# transponder-6_2_0.net
KiCad netlist of a schematic drawn in EAGLE
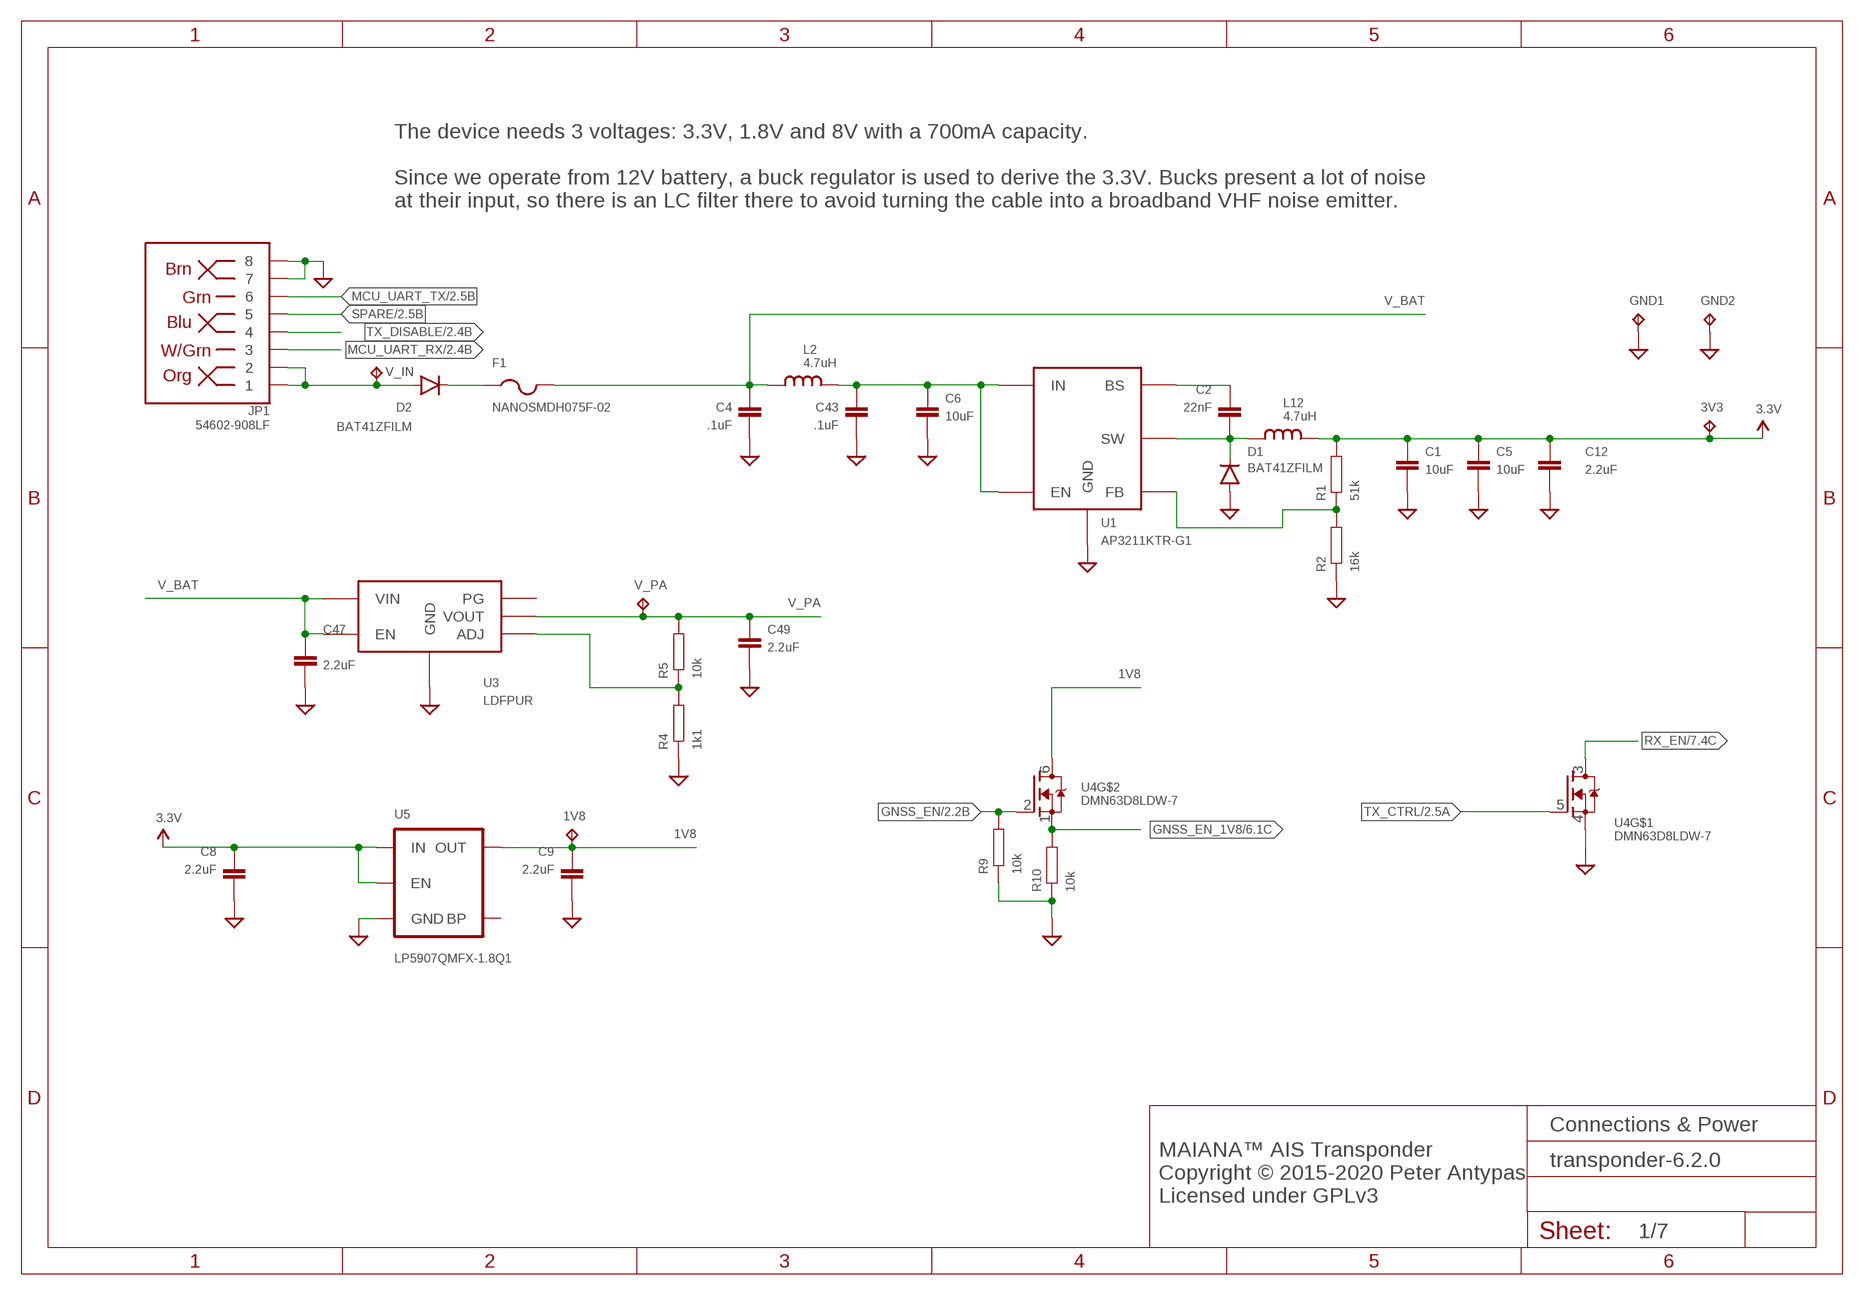
[diagram p0: schematic, sheet 1]
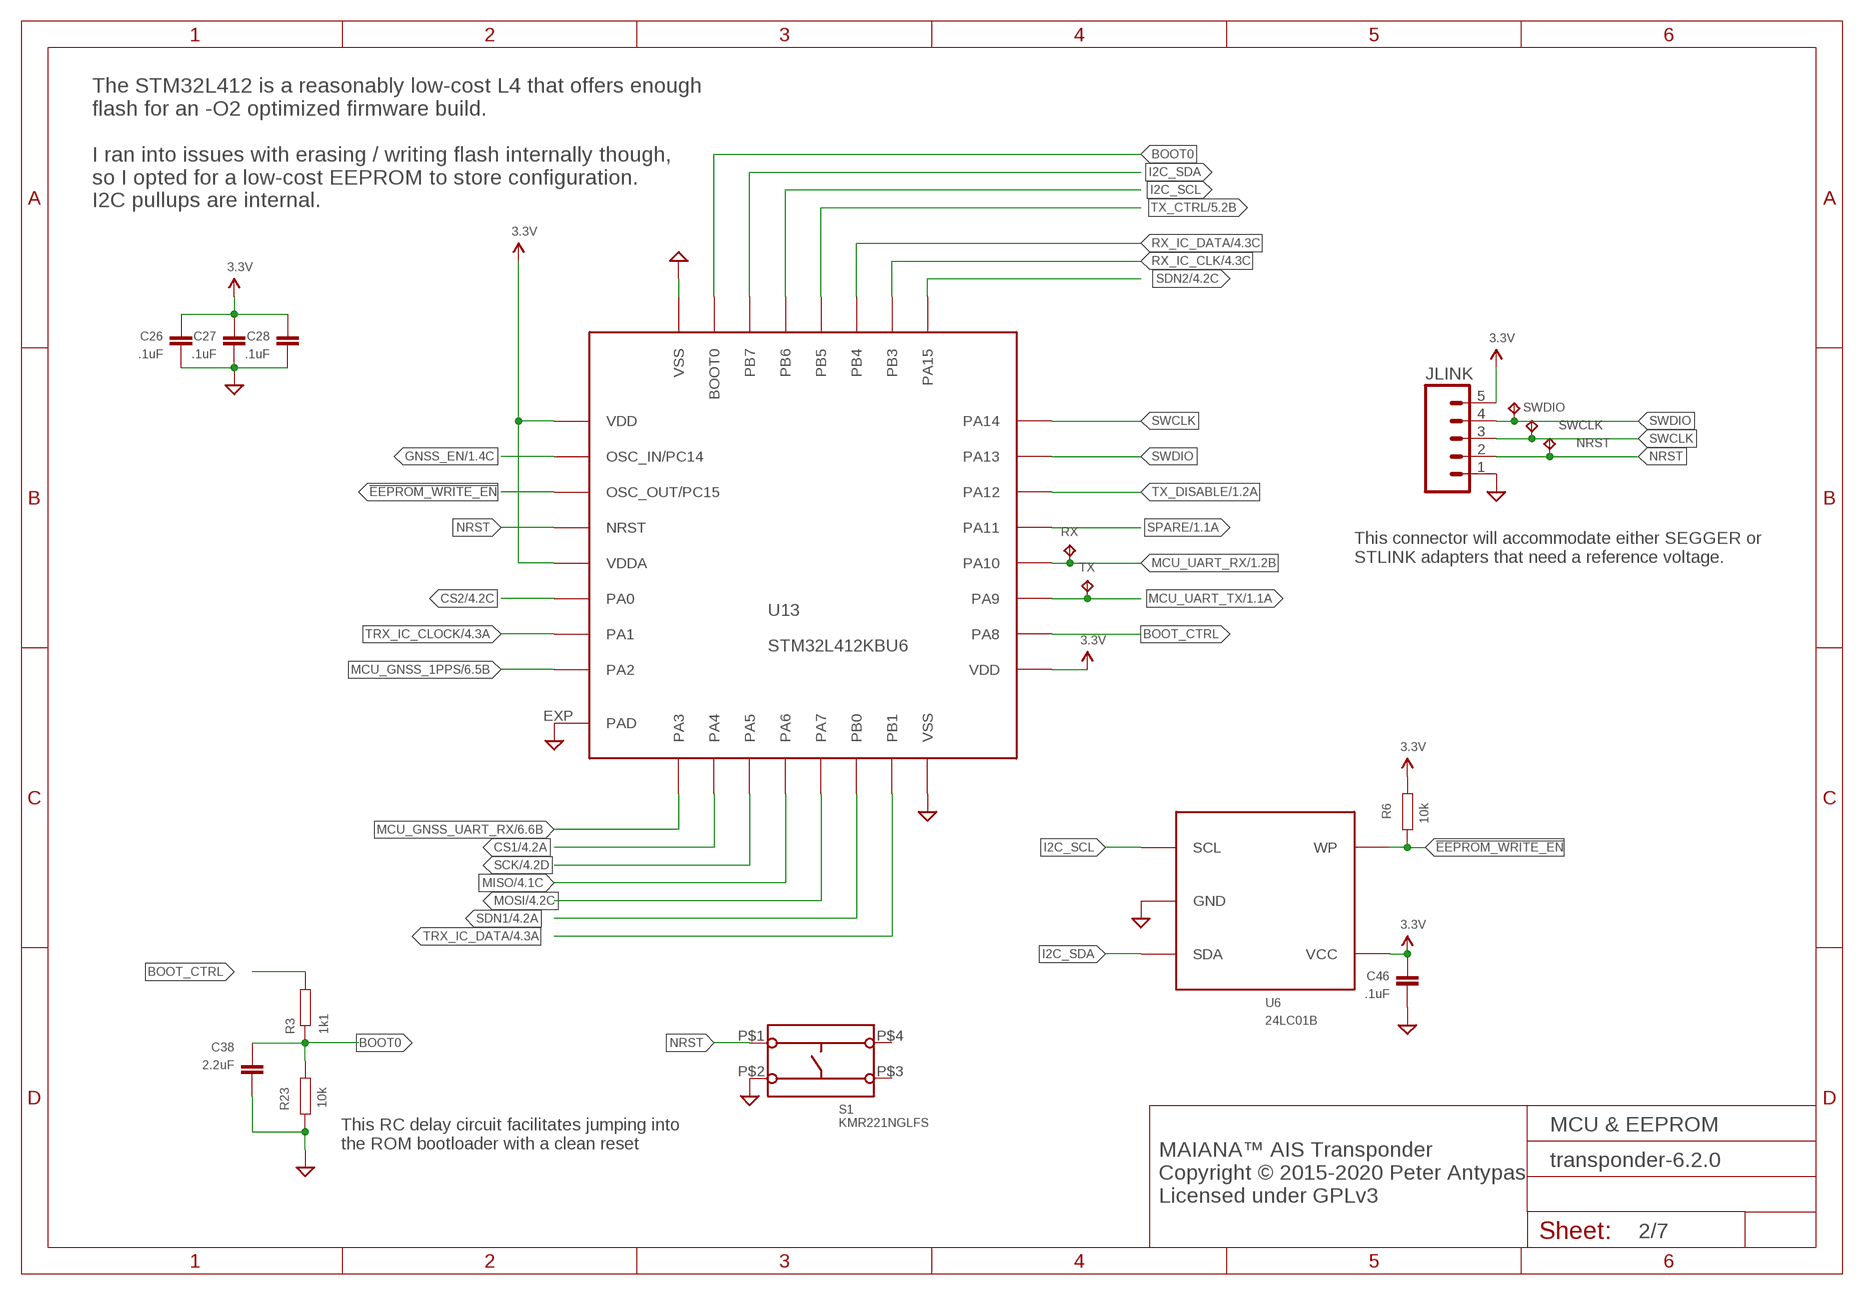
[diagram p1: schematic, sheet 2]
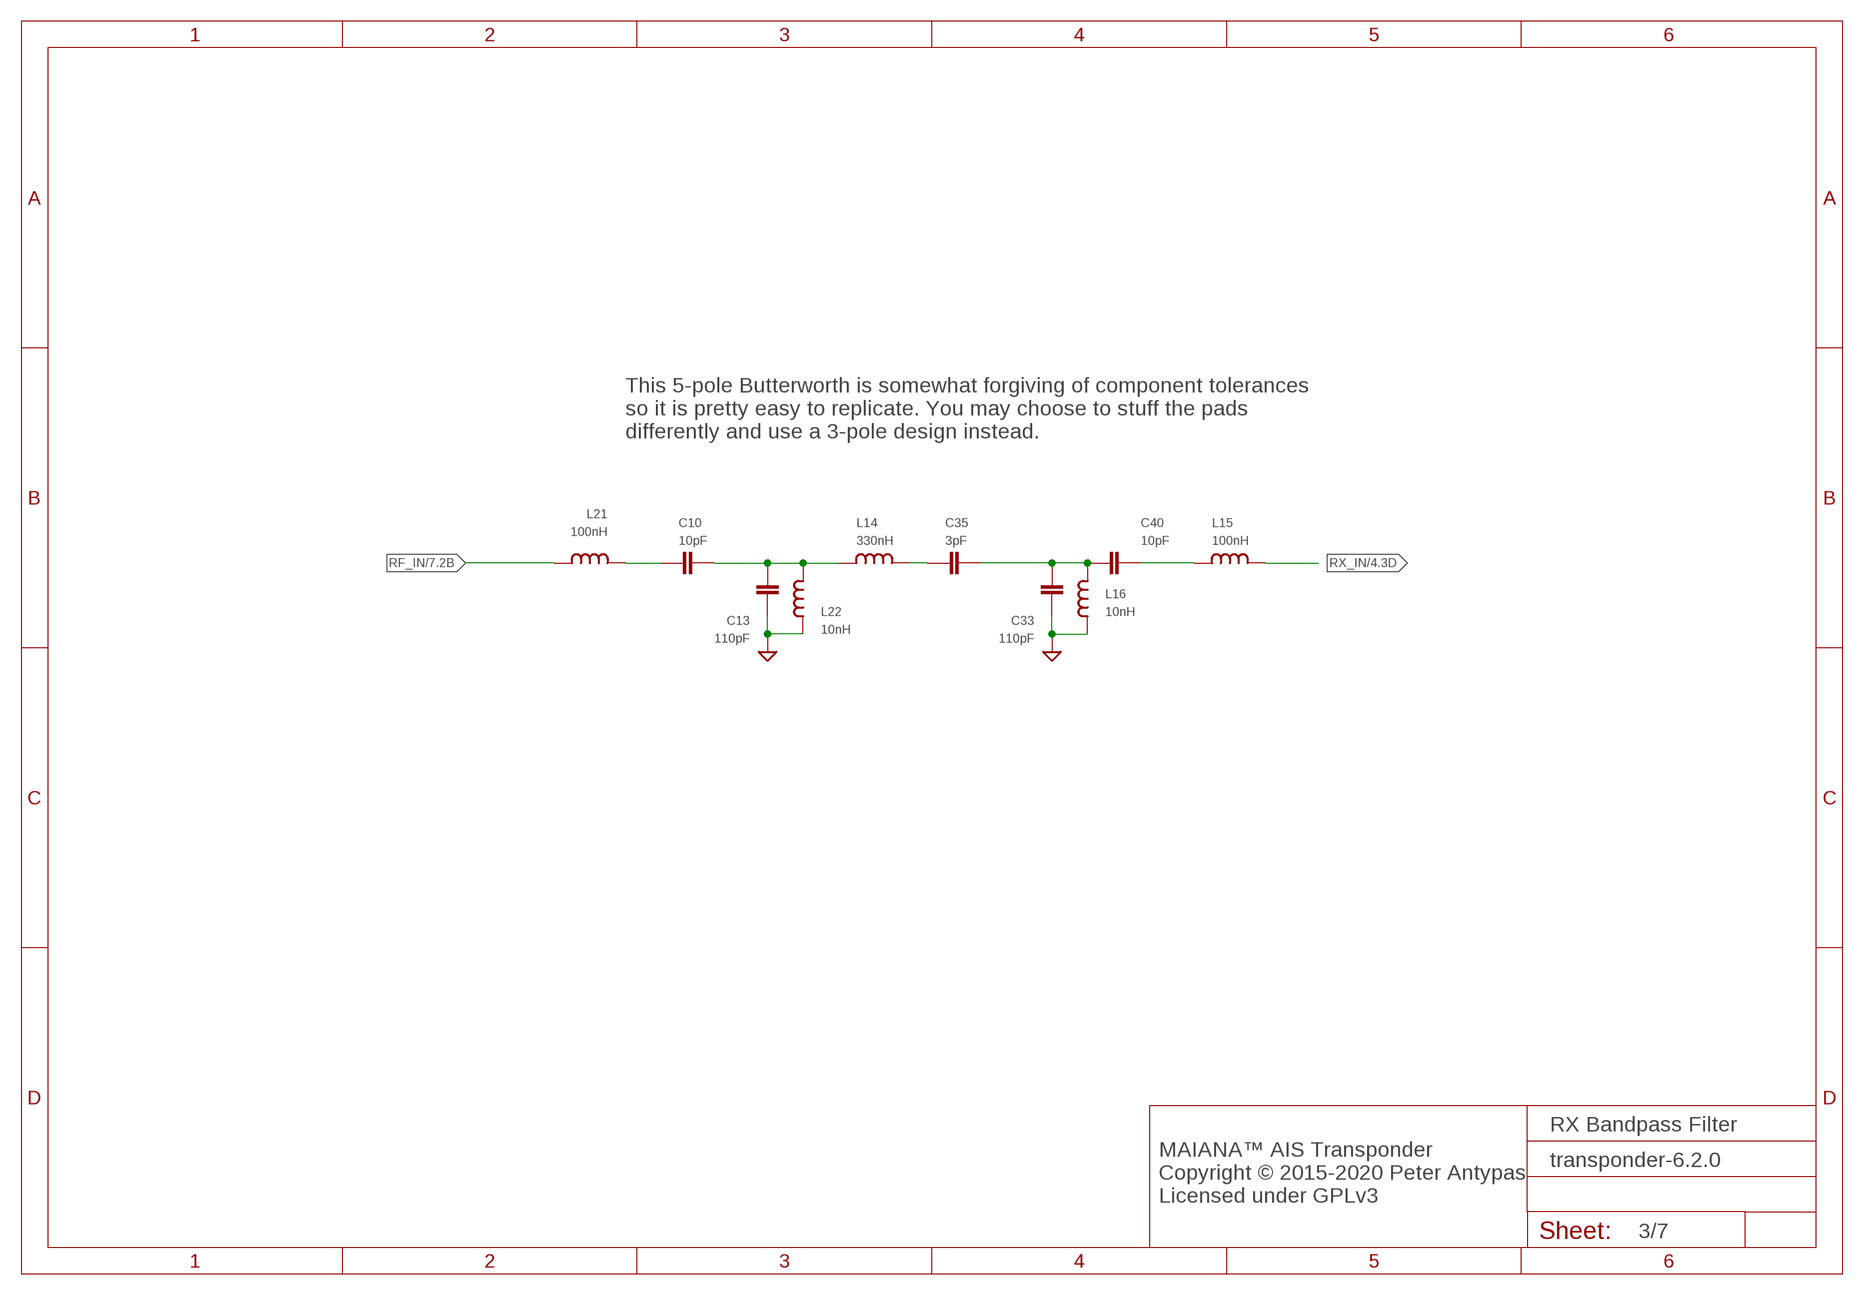
[diagram p2: schematic, sheet 3]
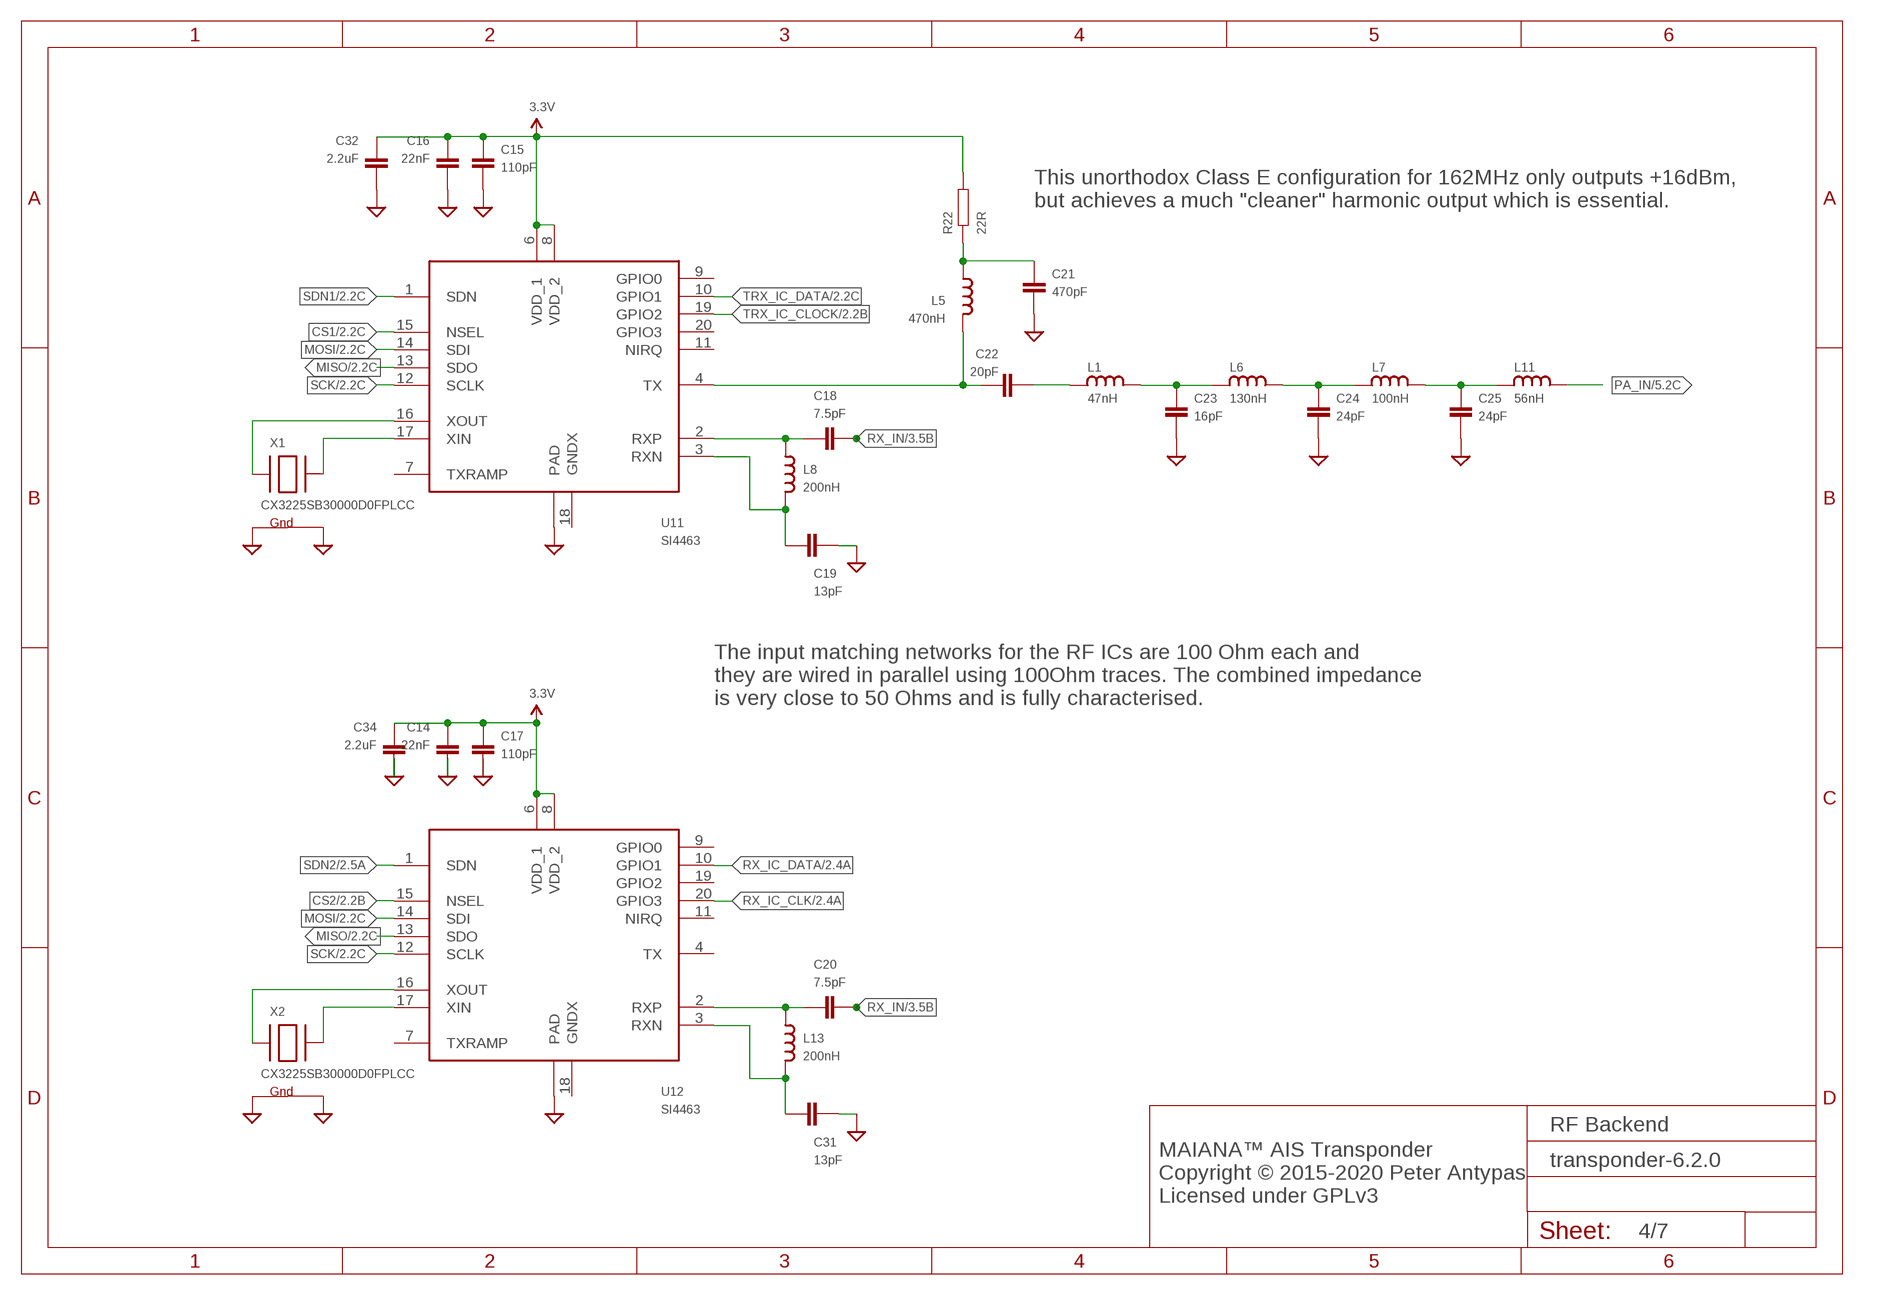
[diagram p3: schematic, sheet 4]
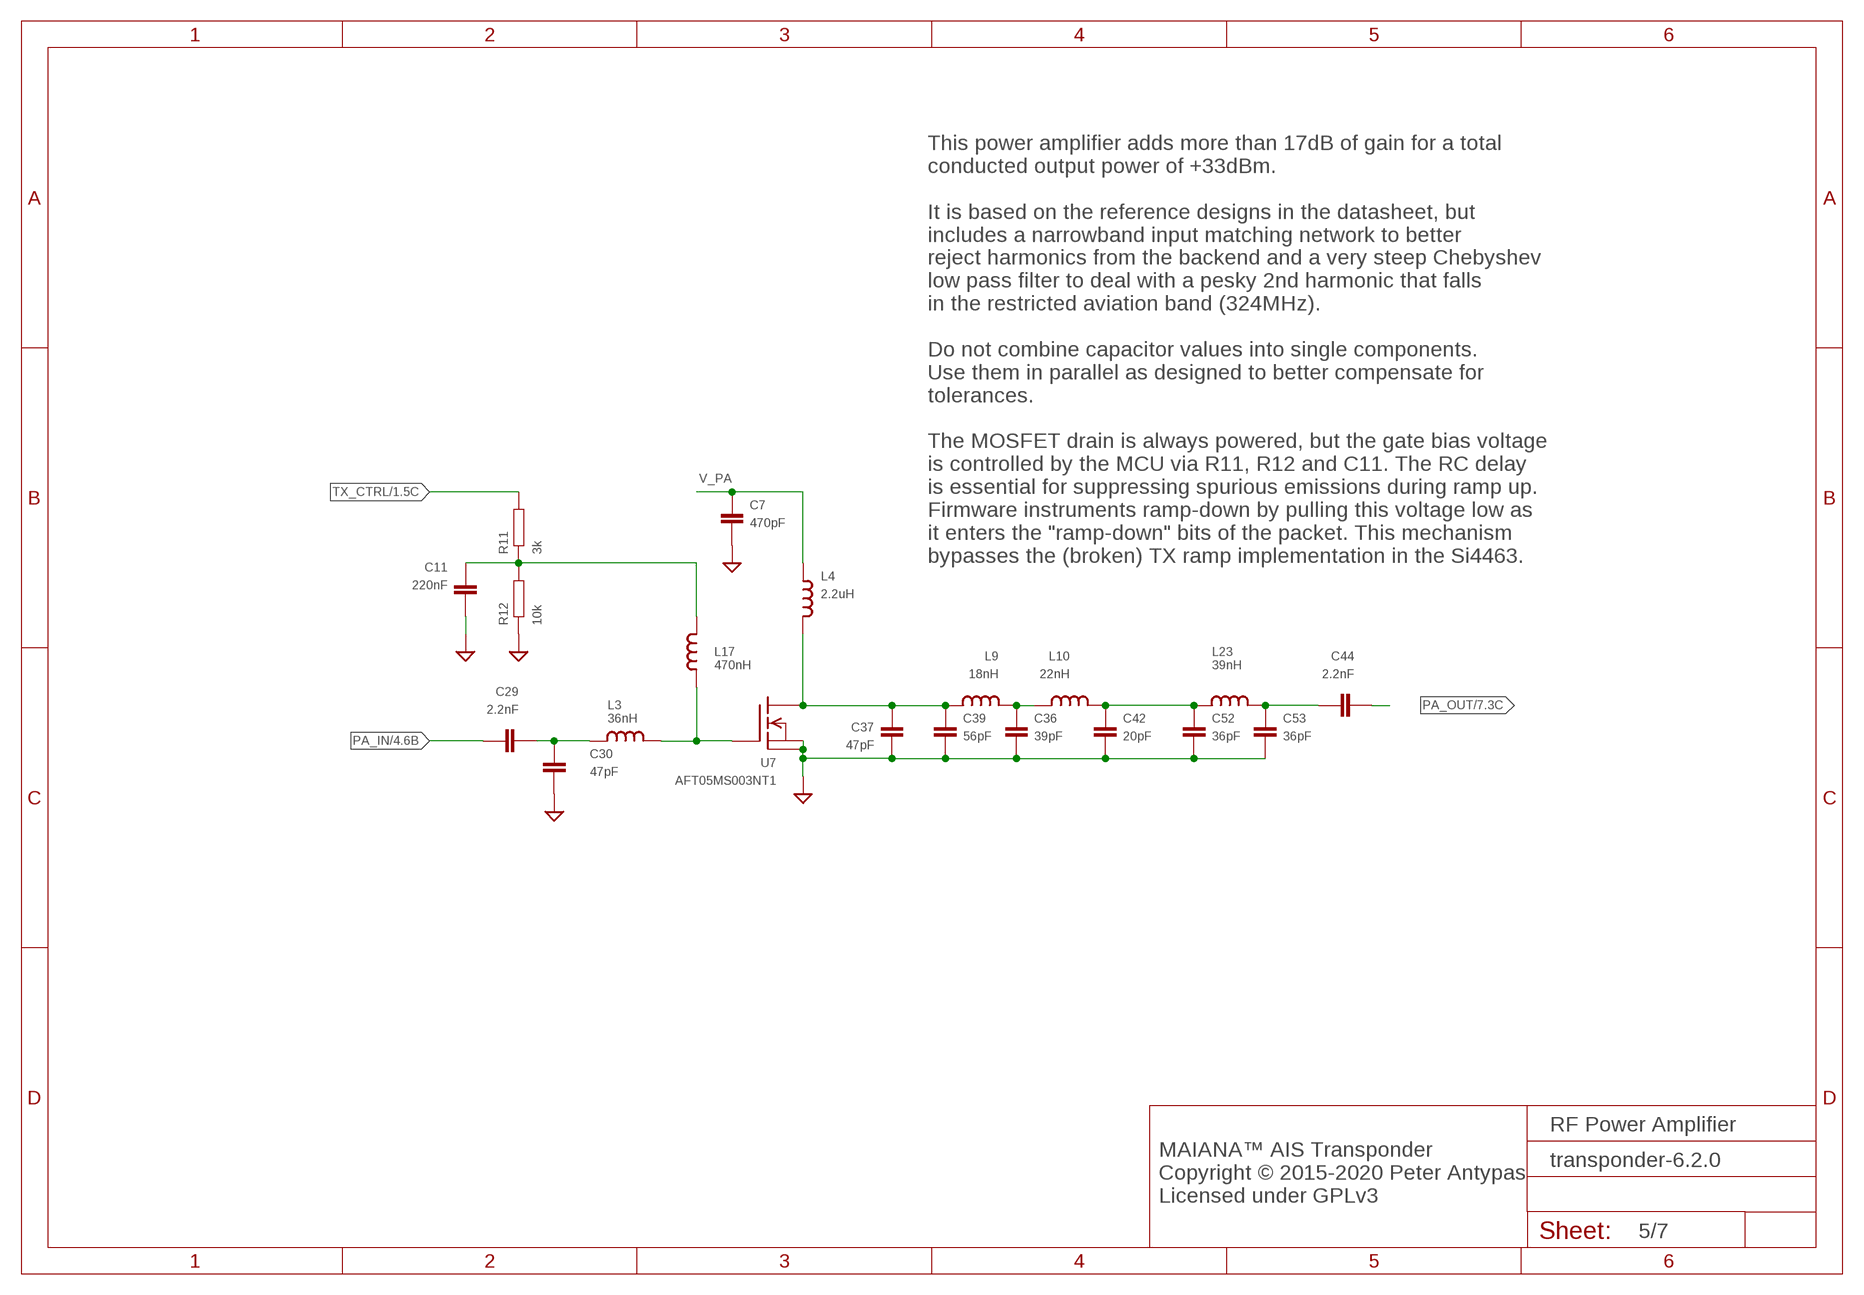
[diagram p4: schematic, sheet 5]
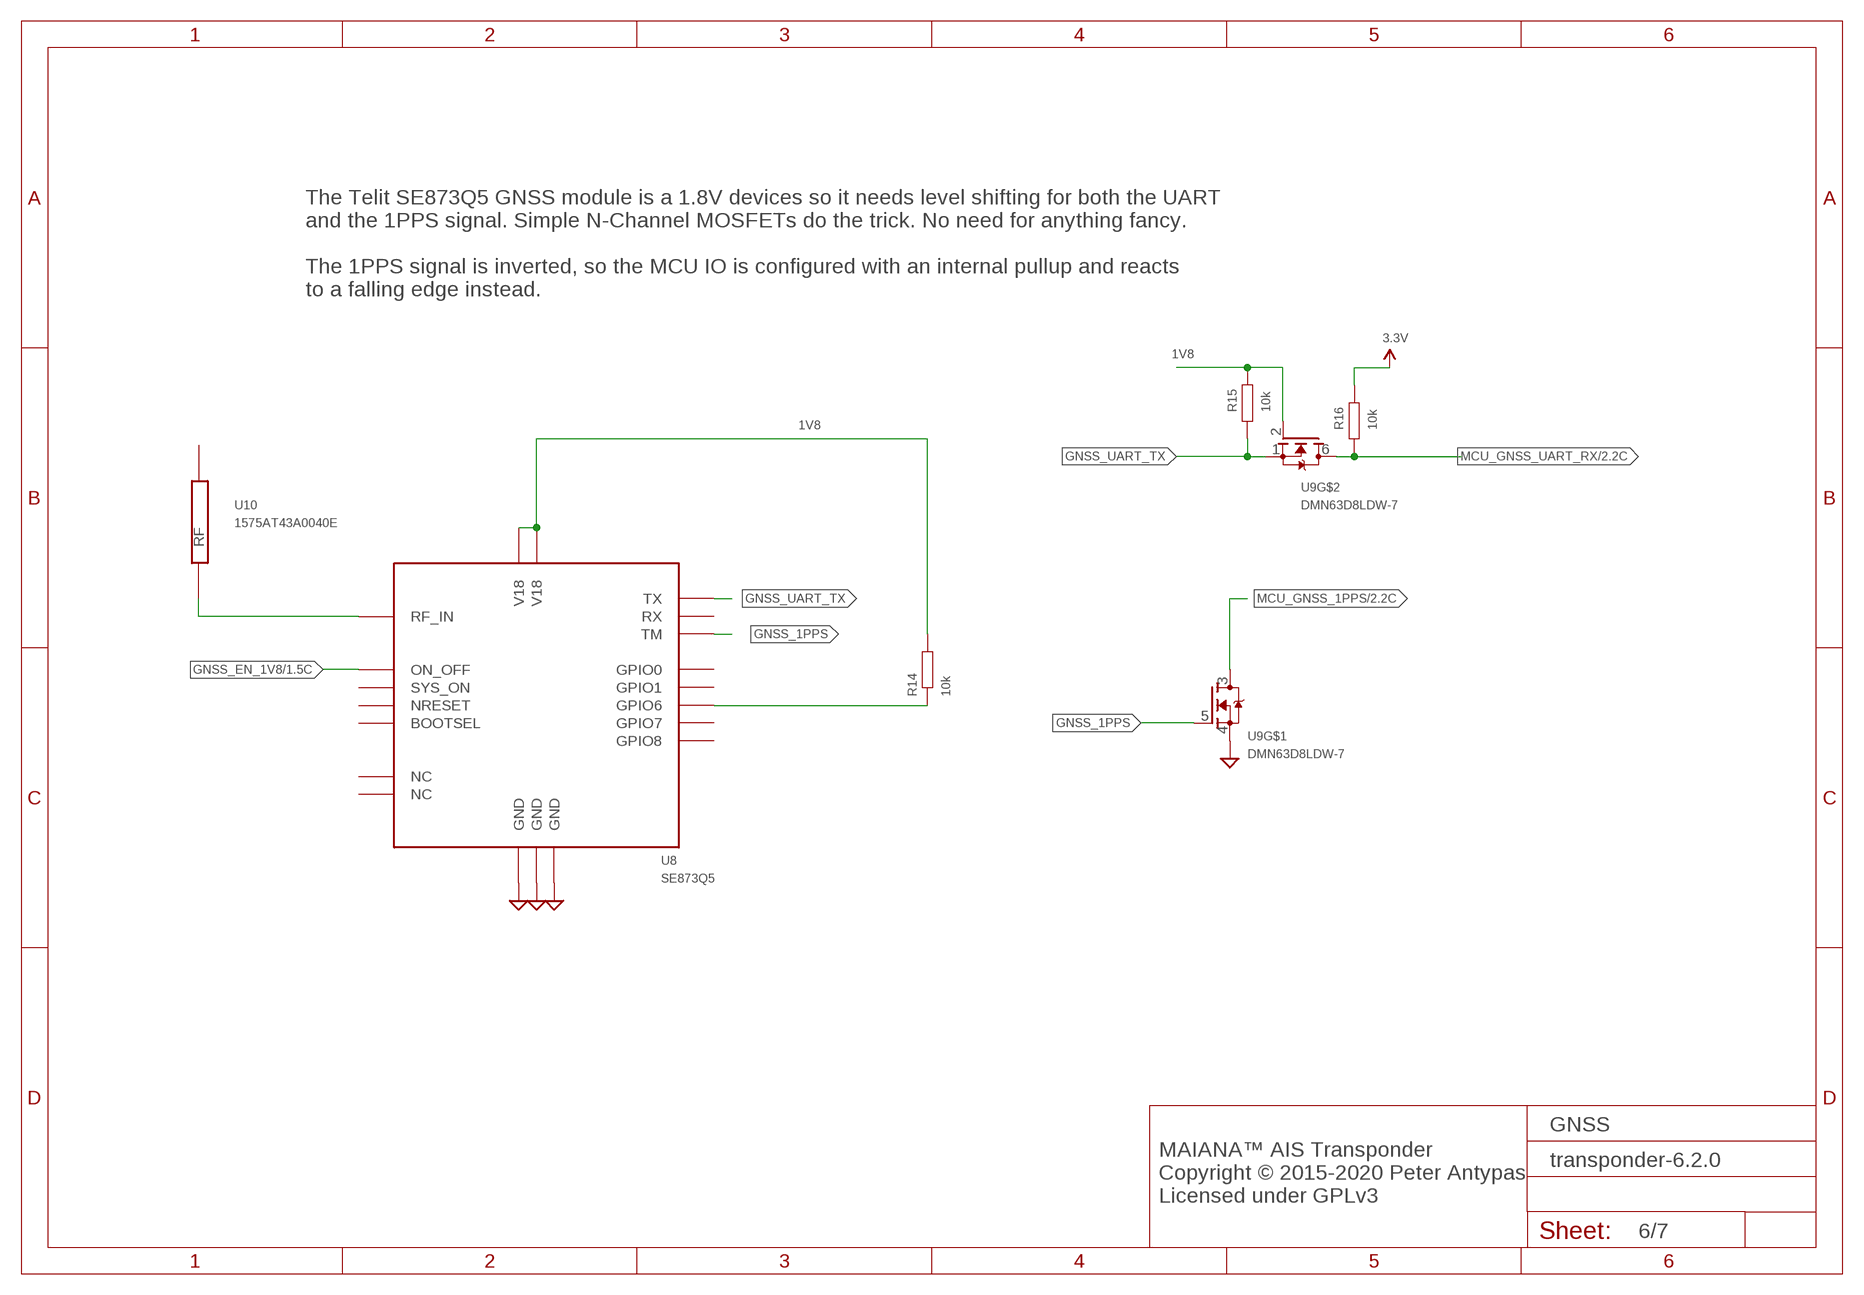
[diagram p5: schematic, sheet 6]
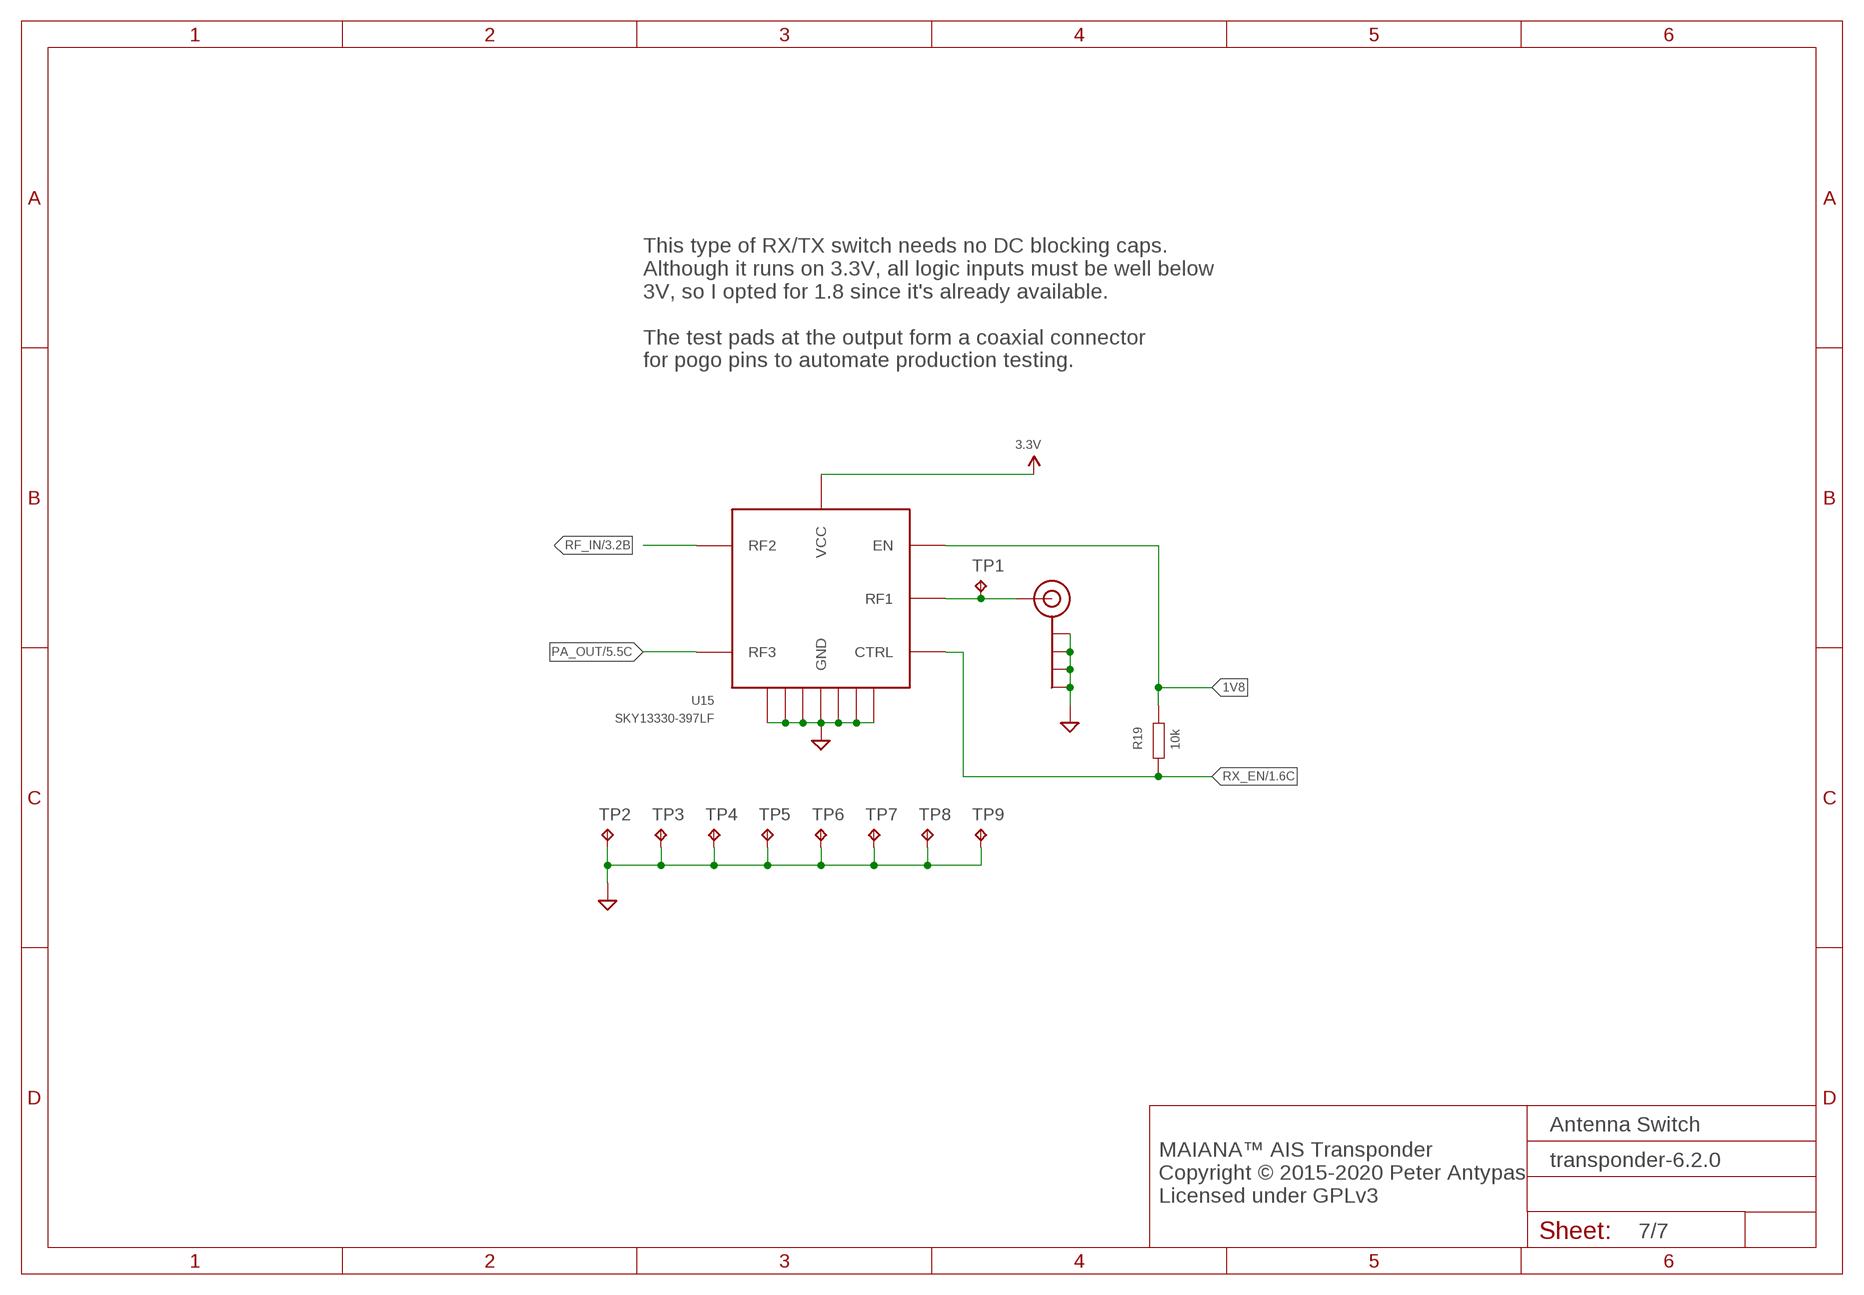
[diagram p6: schematic, sheet 7]

(export (version "E")
  (design (tool "Eeschema 10.0.6"))
  (components
    (comp (ref "R14")
      (value "10k")
      (footprint "eagle-import:0603-RES")
      (fields (field (name "PARTNO") "RC0603JR-0710KL"))
      (libsource (lib "eagle-import") (part "RESISTOR0603-RES"))
    )
    (comp (ref "R15")
      (value "10k")
      (footprint "eagle-import:0603-RES")
      (fields (field (name "PARTNO") "RC0603JR-0710KL"))
      (libsource (lib "eagle-import") (part "RESISTOR0603-RES"))
    )
    (comp (ref "R16")
      (value "10k")
      (footprint "eagle-import:0603-RES")
      (fields (field (name "PARTNO") "RC0603JR-0710KL"))
      (libsource (lib "eagle-import") (part "RESISTOR0603-RES"))
    )
    (comp (ref "U8")
      (value "SE873Q5")
      (footprint "eagle-import:SE873")
      (libsource (lib "eagle-import") (part "SE873"))
    )
    (comp (ref "U9")
      (value "DMN63D8LDW-7")
      (footprint "eagle-import:SOT363")
      (fields (field (name "PARTNO") "DMN63D8LDW-7"))
      (libsource (lib "eagle-import") (part "DMN63D8LDW"))
    )
    (comp (ref "U10")
      (value "1575AT43A0040E")
      (footprint "eagle-import:1575AT43A0040E")
      (libsource (lib "eagle-import") (part "1575AT43A0040E"))
    )
    (comp (ref "C10")
      (value "10pF")
      (footprint "eagle-import:0603")
      (fields (field (name "PARTNO") "GCM1885C2A100FA16D"))
      (libsource (lib "eagle-import") (part "CAPACITOR0603"))
    )
    (comp (ref "C13")
      (value "110pF")
      (footprint "eagle-import:0603")
      (fields (field (name "PARTNO") "GRM1885C2A111JA01D"))
      (libsource (lib "eagle-import") (part "CAPACITOR0603"))
    )
    (comp (ref "C33")
      (value "110pF")
      (footprint "eagle-import:0603")
      (fields (field (name "PARTNO") "GRM1885C2A111JA01D"))
      (libsource (lib "eagle-import") (part "CAPACITOR0603"))
    )
    (comp (ref "C35")
      (value "3pF")
      (footprint "eagle-import:0603")
      (fields (field (name "PARTNO") "06035A3R0CAT2A"))
      (libsource (lib "eagle-import") (part "CAPACITOR0603"))
    )
    (comp (ref "C40")
      (value "10pF")
      (footprint "eagle-import:0603")
      (fields (field (name "PARTNO") "GCM1885C2A100FA16D"))
      (libsource (lib "eagle-import") (part "CAPACITOR0603"))
    )
    (comp (ref "L14")
      (value "330nH")
      (footprint "eagle-import:0603")
      (fields (field (name "PARTNO") "LQW18ANR33G00D"))
      (libsource (lib "eagle-import") (part "INDUCTOR0603"))
    )
    (comp (ref "L15")
      (value "100nH")
      (footprint "eagle-import:0603")
      (fields (field (name "PARTNO") "LQW18ANR10G00D"))
      (libsource (lib "eagle-import") (part "INDUCTOR0603"))
    )
    (comp (ref "L16")
      (value "10nH")
      (footprint "eagle-import:0603")
      (fields (field (name "PARTNO") "LQW18AN10NG00D"))
      (libsource (lib "eagle-import") (part "INDUCTOR0603"))
    )
    (comp (ref "L21")
      (value "100nH")
      (footprint "eagle-import:0603")
      (fields (field (name "PARTNO") "LQW18ANR10G00D"))
      (libsource (lib "eagle-import") (part "INDUCTOR0603"))
    )
    (comp (ref "L22")
      (value "10nH")
      (footprint "eagle-import:0603")
      (fields (field (name "PARTNO") "LQW18AN10NG00D"))
      (libsource (lib "eagle-import") (part "INDUCTOR0603"))
    )
    (comp (ref "C7")
      (value "470pF")
      (footprint "eagle-import:0603")
      (fields (field (name "PARTNO") "GRM1885C1H471JA01D"))
      (libsource (lib "eagle-import") (part "CAPACITOR0603"))
    )
    (comp (ref "C11")
      (value "220nF")
      (footprint "eagle-import:0603")
      (fields (field (name "PARTNO") "C0603C224K4RECAUTO"))
      (libsource (lib "eagle-import") (part "CAPACITOR0603"))
    )
    (comp (ref "C29")
      (value "2.2nF")
      (footprint "eagle-import:0603")
      (fields (field (name "PARTNO") "GRM1885C1H222JA01J"))
      (libsource (lib "eagle-import") (part "CAPACITOR0603"))
    )
    (comp (ref "C30")
      (value "47pF")
      (footprint "eagle-import:0603")
      (fields (field (name "PARTNO") "GRM1885C1H470JA01J"))
      (libsource (lib "eagle-import") (part "CAPACITOR0603"))
    )
    (comp (ref "C36")
      (value "39pF")
      (footprint "eagle-import:0603")
      (fields (field (name "PARTNO") "GRM1885C1H390JA01D"))
      (libsource (lib "eagle-import") (part "CAPACITOR0603"))
    )
    (comp (ref "C37")
      (value "47pF")
      (footprint "eagle-import:0603")
      (fields (field (name "PARTNO") "Murata Electronics"))
      (libsource (lib "eagle-import") (part "CAPACITOR0603"))
    )
    (comp (ref "C39")
      (value "56pF")
      (footprint "eagle-import:0603")
      (fields (field (name "PARTNO") "GRM1885C1H560JA01D"))
      (libsource (lib "eagle-import") (part "CAPACITOR0603"))
    )
    (comp (ref "C42")
      (value "20pF")
      (footprint "eagle-import:0603")
      (fields (field (name "PARTNO") "GRM1885C1H200JA01D"))
      (libsource (lib "eagle-import") (part "CAPACITOR0603"))
    )
    (comp (ref "C44")
      (value "2.2nF")
      (footprint "eagle-import:0603")
      (fields (field (name "PARTNO") "GRM1885C1H222JA01J"))
      (libsource (lib "eagle-import") (part "CAPACITOR0603"))
    )
    (comp (ref "C52")
      (value "36pF")
      (footprint "eagle-import:0603")
      (fields (field (name "PARTNO") "06035A360JAT2A"))
      (libsource (lib "eagle-import") (part "CAPACITOR0603"))
    )
    (comp (ref "C53")
      (value "36pF")
      (footprint "eagle-import:0603")
      (fields (field (name "PARTNO") "06035A360JAT2A"))
      (libsource (lib "eagle-import") (part "CAPACITOR0603"))
    )
    (comp (ref "L3")
      (value "36nH")
      (footprint "eagle-import:0603")
      (fields (field (name "PARTNO") "LQW18AN36NG00D"))
      (libsource (lib "eagle-import") (part "INDUCTOR0603"))
    )
    (comp (ref "L4")
      (value "2.2uH")
      (footprint "eagle-import:0805")
      (fields (field (name "PARTNO") "BRC2012T2R2MD"))
      (libsource (lib "eagle-import") (part "INDUCTOR0805"))
    )
    (comp (ref "L9")
      (value "18nH")
      (footprint "eagle-import:0603")
      (fields (field (name "PARTNO") "LQW18AN18NG00D"))
      (libsource (lib "eagle-import") (part "INDUCTOR0603"))
    )
    (comp (ref "L10")
      (value "22nH")
      (footprint "eagle-import:0603")
      (fields (field (name "PARTNO") "LQW18AN22NJ00D"))
      (libsource (lib "eagle-import") (part "INDUCTOR0603"))
    )
    (comp (ref "L17")
      (value "470nH")
      (footprint "eagle-import:0603")
      (fields (field (name "PARTNO") "HK1608R47J-T"))
      (libsource (lib "eagle-import") (part "INDUCTOR0603"))
    )
    (comp (ref "L23")
      (value "39nH")
      (footprint "eagle-import:0603")
      (fields (field (name "PARTNO") "LQW18AN39NG00D"))
      (libsource (lib "eagle-import") (part "INDUCTOR0603"))
    )
    (comp (ref "R11")
      (value "3k")
      (footprint "eagle-import:0603-RES")
      (fields (field (name "PARTNO") "RC0603JR-073KL"))
      (libsource (lib "eagle-import") (part "RESISTOR0603-RES"))
    )
    (comp (ref "R12")
      (value "10k")
      (footprint "eagle-import:0603-RES")
      (fields (field (name "PARTNO") "RC0603JR-0710KL"))
      (libsource (lib "eagle-import") (part "RESISTOR0603-RES"))
    )
    (comp (ref "U7")
      (value "AFT05MS003NT1")
      (footprint "eagle-import:SOT-89")
      (libsource (lib "eagle-import") (part "AFT0SMS003N"))
    )
    (comp (ref "C26")
      (value ".1uF")
      (footprint "eagle-import:0603")
      (fields (field (name "PARTNO") "EMK107B7104KAHT"))
      (libsource (lib "eagle-import") (part "CAPACITOR0603"))
    )
    (comp (ref "C27")
      (value ".1uF")
      (footprint "eagle-import:0603")
      (fields (field (name "PARTNO") "EMK107B7104KAHT"))
      (libsource (lib "eagle-import") (part "CAPACITOR0603"))
    )
    (comp (ref "C28")
      (value ".1uF")
      (footprint "eagle-import:0603")
      (fields (field (name "PARTNO") "EMK107B7104KAHT"))
      (libsource (lib "eagle-import") (part "CAPACITOR0603"))
    )
    (comp (ref "C38")
      (value "2.2uF")
      (footprint "eagle-import:0603")
      (fields (field (name "PARTNO") "EMK107BJ225KA-T"))
      (libsource (lib "eagle-import") (part "CAPACITOR0603"))
    )
    (comp (ref "C46")
      (value ".1uF")
      (footprint "eagle-import:0603")
      (fields (field (name "PARTNO") "EMK107B7104KAHT"))
      (libsource (lib "eagle-import") (part "CAPACITOR0603"))
    )
    (comp (ref "JLINK")
      (value "M05PTH")
      (footprint "eagle-import:1X05")
      (libsource (lib "eagle-import") (part "M05PTH"))
    )
    (comp (ref "NRST")
      (value "TPTP12R")
      (footprint "eagle-import:TP12R")
      (libsource (lib "eagle-import") (part "TPTP12R"))
    )
    (comp (ref "R3")
      (value "1k1")
      (footprint "eagle-import:0603-RES")
      (fields (field (name "PARTNO") "RC0603JR-071K1L"))
      (libsource (lib "eagle-import") (part "RESISTOR0603-RES"))
    )
    (comp (ref "R6")
      (value "10k")
      (footprint "eagle-import:0603-RES")
      (fields (field (name "PARTNO") "RC0603JR-0710KL"))
      (libsource (lib "eagle-import") (part "RESISTOR0603-RES"))
    )
    (comp (ref "R23")
      (value "10k")
      (footprint "eagle-import:0603-RES")
      (fields (field (name "PARTNO") "RC0603JR-0710KL"))
      (libsource (lib "eagle-import") (part "RESISTOR0603-RES"))
    )
    (comp (ref "RX")
      (value "TPTP12R")
      (footprint "eagle-import:TP12R")
      (libsource (lib "eagle-import") (part "TPTP12R"))
    )
    (comp (ref "S1")
      (value "KMR221NGLFS")
      (footprint "eagle-import:KMR221NGLFS")
      (libsource (lib "eagle-import") (part "KMR221NGLFS"))
    )
    (comp (ref "SWCLK")
      (value "TPTP12R")
      (footprint "eagle-import:TP12R")
      (libsource (lib "eagle-import") (part "TPTP12R"))
    )
    (comp (ref "SWDIO")
      (value "TPTP12R")
      (footprint "eagle-import:TP12R")
      (libsource (lib "eagle-import") (part "TPTP12R"))
    )
    (comp (ref "TX")
      (value "TPTP12R")
      (footprint "eagle-import:TP12R")
      (libsource (lib "eagle-import") (part "TPTP12R"))
    )
    (comp (ref "U6")
      (value "24LC01B")
      (footprint "eagle-import:SOT23-5")
      (fields (field (name "PARTNO") "24LC01BT-I/OT"))
      (libsource (lib "eagle-import") (part "24LC01B"))
    )
    (comp (ref "U13")
      (value "STM32L412KBU6")
      (footprint "eagle-import:QFN32")
      (libsource (lib "eagle-import") (part "STM32L432KXXX"))
    )
    (comp (ref "1V8")
      (value "TPTP12R")
      (footprint "eagle-import:TP12R")
      (libsource (lib "eagle-import") (part "TPTP12R"))
    )
    (comp (ref "3V3")
      (value "TPTP16R")
      (footprint "eagle-import:TP16R")
      (libsource (lib "eagle-import") (part "TPTP16R"))
    )
    (comp (ref "C1")
      (value "10uF")
      (footprint "eagle-import:0805")
      (fields (field (name "PARTNO") " EMK212ABJ106KG-T"))
      (libsource (lib "eagle-import") (part "CAPACITOR0805"))
    )
    (comp (ref "C2")
      (value "22nF")
      (footprint "eagle-import:0603")
      (fields (field (name "PARTNO") "GRM188R71E223KA01D"))
      (libsource (lib "eagle-import") (part "CAPACITOR0603"))
    )
    (comp (ref "C4")
      (value ".1uF")
      (footprint "eagle-import:0603")
      (fields (field (name "PARTNO") "EMK107B7104KAHT"))
      (libsource (lib "eagle-import") (part "CAPACITOR0603"))
    )
    (comp (ref "C5")
      (value "10uF")
      (footprint "eagle-import:0805")
      (fields (field (name "PARTNO") " EMK212ABJ106KG-T"))
      (libsource (lib "eagle-import") (part "CAPACITOR0805"))
    )
    (comp (ref "C6")
      (value "10uF")
      (footprint "eagle-import:0805")
      (fields (field (name "PARTNO") " EMK212ABJ106KG-T"))
      (libsource (lib "eagle-import") (part "CAPACITOR0805"))
    )
    (comp (ref "C8")
      (value "2.2uF")
      (footprint "eagle-import:0603")
      (fields (field (name "PARTNO") "EMK107BJ225KA-T"))
      (libsource (lib "eagle-import") (part "CAPACITOR0603"))
    )
    (comp (ref "C9")
      (value "2.2uF")
      (footprint "eagle-import:0603")
      (fields (field (name "PARTNO") "EMK107BJ225KA-T"))
      (libsource (lib "eagle-import") (part "CAPACITOR0603"))
    )
    (comp (ref "C12")
      (value "2.2uF")
      (footprint "eagle-import:0603")
      (fields (field (name "PARTNO") "EMK107BJ225KA-T"))
      (libsource (lib "eagle-import") (part "CAPACITOR0603"))
    )
    (comp (ref "C43")
      (value ".1uF")
      (footprint "eagle-import:0603")
      (fields (field (name "PARTNO") "EMK107B7104KAHT"))
      (libsource (lib "eagle-import") (part "CAPACITOR0603"))
    )
    (comp (ref "C47")
      (value "2.2uF")
      (footprint "eagle-import:0603")
      (fields (field (name "PARTNO") "EMK107BJ225KA-T"))
      (libsource (lib "eagle-import") (part "CAPACITOR0603"))
    )
    (comp (ref "C49")
      (value "2.2uF")
      (footprint "eagle-import:0603")
      (fields (field (name "PARTNO") "EMK107BJ225KA-T"))
      (libsource (lib "eagle-import") (part "CAPACITOR0603"))
    )
    (comp (ref "D1")
      (value "BAT41ZFILM")
      (footprint "eagle-import:SOD-123")
      (libsource (lib "eagle-import") (part "DIODESOD123"))
    )
    (comp (ref "D2")
      (value "BAT41ZFILM")
      (footprint "eagle-import:SOD-123")
      (libsource (lib "eagle-import") (part "DIODESOD123"))
    )
    (comp (ref "F1")
      (value "NANOSMDH075F-02")
      (footprint "eagle-import:R1206")
      (libsource (lib "eagle-import") (part "PTCFUSE-1206"))
    )
    (comp (ref "GND1")
      (value "TPTP16R")
      (footprint "eagle-import:TP16R")
      (libsource (lib "eagle-import") (part "TPTP16R"))
    )
    (comp (ref "GND2")
      (value "TPTP16R")
      (footprint "eagle-import:TP16R")
      (libsource (lib "eagle-import") (part "TPTP16R"))
    )
    (comp (ref "JP1")
      (value "54602-908LF")
      (footprint "eagle-import:RJ45-8")
      (libsource (lib "eagle-import") (part "RJ45-8PTH"))
    )
    (comp (ref "L2")
      (value "4.7uH")
      (footprint "eagle-import:0805")
      (fields (field (name "PARTNO") "MLZ2012M4R7WT000"))
      (libsource (lib "eagle-import") (part "INDUCTOR0805"))
    )
    (comp (ref "L12")
      (value "4.7uH")
      (footprint "eagle-import:0805")
      (fields (field (name "PARTNO") "MLZ2012M4R7WT000"))
      (libsource (lib "eagle-import") (part "INDUCTOR0805"))
    )
    (comp (ref "R1")
      (value "51k")
      (footprint "eagle-import:0603-RES")
      (fields (field (name "PARTNO") "RC0603JR-0751KL"))
      (libsource (lib "eagle-import") (part "RESISTOR0603-RES"))
    )
    (comp (ref "R2")
      (value "16k")
      (footprint "eagle-import:0603-RES")
      (fields (field (name "PARTNO") "RC0603JR-0716KL‎"))
      (libsource (lib "eagle-import") (part "RESISTOR0603-RES"))
    )
    (comp (ref "R4")
      (value "1k1")
      (footprint "eagle-import:0603-RES")
      (fields (field (name "PARTNO") "RC0603JR-071K1L"))
      (libsource (lib "eagle-import") (part "RESISTOR0603-RES"))
    )
    (comp (ref "R5")
      (value "10k")
      (footprint "eagle-import:0603-RES")
      (fields (field (name "PARTNO") "RC0603JR-0710KL"))
      (libsource (lib "eagle-import") (part "RESISTOR0603-RES"))
    )
    (comp (ref "R9")
      (value "10k")
      (footprint "eagle-import:0603-RES")
      (fields (field (name "PARTNO") "RC0603JR-0710KL"))
      (libsource (lib "eagle-import") (part "RESISTOR0603-RES"))
    )
    (comp (ref "R10")
      (value "10k")
      (footprint "eagle-import:0603-RES")
      (fields (field (name "PARTNO") "RC0603JR-0710KL"))
      (libsource (lib "eagle-import") (part "RESISTOR0603-RES"))
    )
    (comp (ref "U1")
      (value "AP3211KTR-G1")
      (footprint "eagle-import:SOT23-6")
      (libsource (lib "eagle-import") (part "AP3211"))
    )
    (comp (ref "U3")
      (value "LDFPUR")
      (footprint "eagle-import:DFN-6")
      (libsource (lib "eagle-import") (part "LDF"))
    )
    (comp (ref "U4")
      (value "DMN63D8LDW-7")
      (footprint "eagle-import:SOT363")
      (fields (field (name "PARTNO") "DMN63D8LDW-7"))
      (libsource (lib "eagle-import") (part "DMN63D8LDW"))
    )
    (comp (ref "U5")
      (value "LP5907QMFX-1.8Q1")
      (footprint "eagle-import:SOT23-5")
      (fields (field (name "PARTNO") "LP5907QMFX-1.8Q1 "))
      (libsource (lib "eagle-import") (part "V_REG_LDOSMD"))
    )
    (comp (ref "V_IN")
      (value "TPTP12R")
      (footprint "eagle-import:TP12R")
      (libsource (lib "eagle-import") (part "TPTP12R"))
    )
    (comp (ref "V_PA")
      (value "TPTP12R")
      (footprint "eagle-import:TP12R")
      (libsource (lib "eagle-import") (part "TPTP12R"))
    )
    (comp (ref "J$1")
      (value "SMA_EDGE")
      (footprint "eagle-import:SMA-EDGE")
      (libsource (lib "eagle-import") (part "SMA_EDGE"))
    )
    (comp (ref "R19")
      (value "10k")
      (footprint "eagle-import:0603-RES")
      (fields (field (name "PARTNO") "RC0603JR-0710KL"))
      (libsource (lib "eagle-import") (part "RESISTOR0603-RES"))
    )
    (comp (ref "TP1")
      (value "TPTP10R")
      (footprint "eagle-import:TP10R")
      (libsource (lib "eagle-import") (part "TPTP10R"))
    )
    (comp (ref "TP2")
      (value "TPTP08R")
      (footprint "eagle-import:TP08R")
      (libsource (lib "eagle-import") (part "TPTP08R"))
    )
    (comp (ref "TP3")
      (value "TPTP08R")
      (footprint "eagle-import:TP08R")
      (libsource (lib "eagle-import") (part "TPTP08R"))
    )
    (comp (ref "TP4")
      (value "TPTP08R")
      (footprint "eagle-import:TP08R")
      (libsource (lib "eagle-import") (part "TPTP08R"))
    )
    (comp (ref "TP5")
      (value "TPTP08R")
      (footprint "eagle-import:TP08R")
      (libsource (lib "eagle-import") (part "TPTP08R"))
    )
    (comp (ref "TP6")
      (value "TPTP08R")
      (footprint "eagle-import:TP08R")
      (libsource (lib "eagle-import") (part "TPTP08R"))
    )
    (comp (ref "TP7")
      (value "TPTP08R")
      (footprint "eagle-import:TP08R")
      (libsource (lib "eagle-import") (part "TPTP08R"))
    )
    (comp (ref "TP8")
      (value "TPTP08R")
      (footprint "eagle-import:TP08R")
      (libsource (lib "eagle-import") (part "TPTP08R"))
    )
    (comp (ref "TP9")
      (value "TPTP08R")
      (footprint "eagle-import:TP08R")
      (libsource (lib "eagle-import") (part "TPTP08R"))
    )
    (comp (ref "U15")
      (value "SKY13330-397LF")
      (footprint "eagle-import:QFN12")
      (libsource (lib "eagle-import") (part "SKYWORKS-13330397LF"))
    )
    (comp (ref "C14")
      (value "22nF")
      (footprint "eagle-import:0603")
      (fields (field (name "PARTNO") "GRM188R71E223KA01D"))
      (libsource (lib "eagle-import") (part "CAPACITOR0603"))
    )
    (comp (ref "C15")
      (value "110pF")
      (footprint "eagle-import:0603")
      (fields (field (name "PARTNO") "GRM1885C2A111JA01D"))
      (libsource (lib "eagle-import") (part "CAPACITOR0603"))
    )
    (comp (ref "C16")
      (value "22nF")
      (footprint "eagle-import:0603")
      (fields (field (name "PARTNO") "GRM188R71E223KA01D"))
      (libsource (lib "eagle-import") (part "CAPACITOR0603"))
    )
    (comp (ref "C17")
      (value "110pF")
      (footprint "eagle-import:0603")
      (fields (field (name "PARTNO") "GRM1885C2A111JA01D"))
      (libsource (lib "eagle-import") (part "CAPACITOR0603"))
    )
    (comp (ref "C18")
      (value "7.5pF")
      (footprint "eagle-import:0603")
      (fields (field (name "PARTNO") "GRM1885C1H7R5DA01D"))
      (libsource (lib "eagle-import") (part "CAPACITOR0603"))
    )
    (comp (ref "C19")
      (value "13pF")
      (footprint "eagle-import:0603")
      (fields (field (name "PARTNO") "GRM1885C1H130JA01D"))
      (libsource (lib "eagle-import") (part "CAPACITOR0603"))
    )
    (comp (ref "C20")
      (value "7.5pF")
      (footprint "eagle-import:0603")
      (fields (field (name "PARTNO") "GRM1885C1H7R5DA01D"))
      (libsource (lib "eagle-import") (part "CAPACITOR0603"))
    )
    (comp (ref "C21")
      (value "470pF")
      (footprint "eagle-import:0603")
      (fields (field (name "PARTNO") "GRM1885C1H471JA01D"))
      (libsource (lib "eagle-import") (part "CAPACITOR0603"))
    )
    (comp (ref "C22")
      (value "20pF")
      (footprint "eagle-import:0603")
      (fields (field (name "PARTNO") "GRM1885C1H200JA01D"))
      (libsource (lib "eagle-import") (part "CAPACITOR0603"))
    )
    (comp (ref "C23")
      (value "16pF")
      (footprint "eagle-import:0603")
      (fields (field (name "PARTNO") "GCM1885C2A160JA16D"))
      (libsource (lib "eagle-import") (part "CAPACITOR0603"))
    )
    (comp (ref "C24")
      (value "24pF")
      (footprint "eagle-import:0603")
      (fields (field (name "PARTNO") "GRM1885C2A240JA01D"))
      (libsource (lib "eagle-import") (part "CAPACITOR0603"))
    )
    (comp (ref "C25")
      (value "24pF")
      (footprint "eagle-import:0603")
      (fields (field (name "PARTNO") "GRM1885C2A240JA01D"))
      (libsource (lib "eagle-import") (part "CAPACITOR0603"))
    )
    (comp (ref "C31")
      (value "13pF")
      (footprint "eagle-import:0603")
      (fields (field (name "PARTNO") "GRM1885C1H130JA01D"))
      (libsource (lib "eagle-import") (part "CAPACITOR0603"))
    )
    (comp (ref "C32")
      (value "2.2uF")
      (footprint "eagle-import:0603")
      (fields (field (name "PARTNO") "EMK107BJ225KA-T"))
      (libsource (lib "eagle-import") (part "CAPACITOR0603"))
    )
    (comp (ref "C34")
      (value "2.2uF")
      (footprint "eagle-import:0603")
      (fields (field (name "PARTNO") "EMK107BJ225KA-T"))
      (libsource (lib "eagle-import") (part "CAPACITOR0603"))
    )
    (comp (ref "L1")
      (value "47nH")
      (footprint "eagle-import:0603")
      (fields (field (name "PARTNO") "LQW18AN47NG00D"))
      (libsource (lib "eagle-import") (part "INDUCTOR0603"))
    )
    (comp (ref "L5")
      (value "470nH")
      (footprint "eagle-import:0603")
      (fields (field (name "PARTNO") "HK1608R47J-T"))
      (libsource (lib "eagle-import") (part "INDUCTOR0603"))
    )
    (comp (ref "L6")
      (value "130nH")
      (footprint "eagle-import:0603")
      (fields (field (name "PARTNO") "LQW18ANR13G00D"))
      (libsource (lib "eagle-import") (part "INDUCTOR0603"))
    )
    (comp (ref "L7")
      (value "100nH")
      (footprint "eagle-import:0603")
      (fields (field (name "PARTNO") "LQW18ANR10G00D"))
      (libsource (lib "eagle-import") (part "INDUCTOR0603"))
    )
    (comp (ref "L8")
      (value "200nH")
      (footprint "eagle-import:0603")
      (fields (field (name "PARTNO") "LQW18ANR20J00D"))
      (libsource (lib "eagle-import") (part "INDUCTOR0603"))
    )
    (comp (ref "L11")
      (value "56nH")
      (footprint "eagle-import:0603")
      (fields (field (name "PARTNO") "LQW18AN56NG00D"))
      (libsource (lib "eagle-import") (part "INDUCTOR0603"))
    )
    (comp (ref "L13")
      (value "200nH")
      (footprint "eagle-import:0603")
      (fields (field (name "PARTNO") "LQW18ANR20J00D"))
      (libsource (lib "eagle-import") (part "INDUCTOR0603"))
    )
    (comp (ref "R22")
      (value "22R")
      (footprint "eagle-import:0603-RES")
      (fields (field (name "PARTNO") "RC0603JR-0722RL"))
      (libsource (lib "eagle-import") (part "RESISTOR0603-RES"))
    )
    (comp (ref "U11")
      (value "SI4463")
      (footprint "eagle-import:SI4463")
      (fields (field (name "PARTNO") "SI4463-C2A-GMR"))
      (libsource (lib "eagle-import") (part "SI4463"))
    )
    (comp (ref "U12")
      (value "SI4463")
      (footprint "eagle-import:SI4463")
      (fields (field (name "PARTNO") "SI4463-C2A-GMR"))
      (libsource (lib "eagle-import") (part "SI4463"))
    )
    (comp (ref "X1")
      (value "CX3225SB30000D0FPLCC")
      (footprint "eagle-import:NX3225")
      (libsource (lib "eagle-import") (part "XTAL-4-3225"))
    )
    (comp (ref "X2")
      (value "CX3225SB30000D0FPLCC")
      (footprint "eagle-import:NX3225")
      (libsource (lib "eagle-import") (part "XTAL-4-3225"))
    )
  )
  (nets
    (net (code "1") (name "1V8") (class "Default")
      (node (ref "1V8") (pin "TP") (pinfunction "TP_TP") (pintype "input"))
      (node (ref "C9") (pin "P$1") (pinfunction "1_P$1") (pintype "passive"))
      (node (ref "R14") (pin "2") (pinfunction "2_2") (pintype "passive"))
      (node (ref "R15") (pin "2") (pinfunction "2_2") (pintype "passive"))
      (node (ref "R19") (pin "2") (pinfunction "2_2") (pintype "passive"))
      (node (ref "U15") (pin "P$8") (pinfunction "EN_P$8") (pintype "bidirectional"))
      (node (ref "U4") (pin "6") (pinfunction "D_6") (pintype "bidirectional"))
      (node (ref "U5") (pin "5") (pinfunction "OUT_5") (pintype "passive"))
      (node (ref "U8") (pin "P$19") (pinfunction "V18_P$19") (pintype "bidirectional"))
      (node (ref "U8") (pin "P$3") (pinfunction "V18_P$3") (pintype "bidirectional"))
      (node (ref "U9") (pin "2") (pinfunction "G_2") (pintype "bidirectional"))
    )
    (net (code "2") (name "3.3V") (class "Default")
      (node (ref "3V3") (pin "TP") (pinfunction "TP_TP") (pintype "input"))
      (node (ref "C1") (pin "P$1") (pinfunction "1_P$1") (pintype "passive"))
      (node (ref "C12") (pin "P$1") (pinfunction "1_P$1") (pintype "passive"))
      (node (ref "C14") (pin "P$1") (pinfunction "1_P$1") (pintype "passive"))
      (node (ref "C15") (pin "P$1") (pinfunction "1_P$1") (pintype "passive"))
      (node (ref "C16") (pin "P$1") (pinfunction "1_P$1") (pintype "passive"))
      (node (ref "C17") (pin "P$1") (pinfunction "1_P$1") (pintype "passive"))
      (node (ref "C26") (pin "P$1") (pinfunction "1_P$1") (pintype "passive"))
      (node (ref "C27") (pin "P$1") (pinfunction "1_P$1") (pintype "passive"))
      (node (ref "C28") (pin "P$1") (pinfunction "1_P$1") (pintype "passive"))
      (node (ref "C32") (pin "P$1") (pinfunction "1_P$1") (pintype "passive"))
      (node (ref "C34") (pin "P$1") (pinfunction "1_P$1") (pintype "passive"))
      (node (ref "C46") (pin "P$1") (pinfunction "1_P$1") (pintype "passive"))
      (node (ref "C5") (pin "P$1") (pinfunction "1_P$1") (pintype "passive"))
      (node (ref "C8") (pin "P$1") (pinfunction "1_P$1") (pintype "passive"))
      (node (ref "JLINK") (pin "5") (pinfunction "5_5") (pintype "passive"))
      (node (ref "L12") (pin "P$2") (pinfunction "2_P$2") (pintype "passive"))
      (node (ref "R1") (pin "2") (pinfunction "2_2") (pintype "passive"))
      (node (ref "R16") (pin "2") (pinfunction "2_2") (pintype "passive"))
      (node (ref "R22") (pin "2") (pinfunction "2_2") (pintype "passive"))
      (node (ref "R6") (pin "1") (pinfunction "1_1") (pintype "passive"))
      (node (ref "U11") (pin "6") (pinfunction "VDD_1_6") (pintype "power_in"))
      (node (ref "U11") (pin "8") (pinfunction "VDD_2_8") (pintype "power_in"))
      (node (ref "U12") (pin "6") (pinfunction "VDD_1_6") (pintype "power_in"))
      (node (ref "U12") (pin "8") (pinfunction "VDD_2_8") (pintype "power_in"))
      (node (ref "U13") (pin "1") (pinfunction "VDD_1") (pintype "bidirectional"))
      (node (ref "U13") (pin "17") (pinfunction "VDD_17") (pintype "bidirectional"))
      (node (ref "U13") (pin "5") (pinfunction "VDDA_5") (pintype "bidirectional"))
      (node (ref "U15") (pin "P$9") (pinfunction "VCC_P$9") (pintype "bidirectional"))
      (node (ref "U5") (pin "1") (pinfunction "IN_1") (pintype "input"))
      (node (ref "U5") (pin "3") (pinfunction "EN_3") (pintype "input"))
      (node (ref "U6") (pin "4") (pinfunction "VCC_4") (pintype "bidirectional"))
    )
    (net (code "3") (name "BOOT0") (class "Default")
      (node (ref "C38") (pin "P$1") (pinfunction "1_P$1") (pintype "passive"))
      (node (ref "R23") (pin "1") (pinfunction "1_1") (pintype "passive"))
      (node (ref "R3") (pin "1") (pinfunction "1_1") (pintype "passive"))
      (node (ref "U13") (pin "31") (pinfunction "BOOT0_31") (pintype "bidirectional"))
    )
    (net (code "4") (name "BOOT_CTRL") (class "Default")
      (node (ref "R3") (pin "2") (pinfunction "2_2") (pintype "passive"))
      (node (ref "U13") (pin "18") (pinfunction "PA8_18") (pintype "bidirectional"))
    )
    (net (code "5") (name "CS1") (class "Default")
      (node (ref "U11") (pin "15") (pinfunction "NSEL_15") (pintype "input"))
      (node (ref "U13") (pin "10") (pinfunction "PA4_10") (pintype "bidirectional"))
    )
    (net (code "6") (name "CS2") (class "Default")
      (node (ref "U12") (pin "15") (pinfunction "NSEL_15") (pintype "input"))
      (node (ref "U13") (pin "6") (pinfunction "PA0_6") (pintype "bidirectional"))
    )
    (net (code "7") (name "GND") (class "Default")
      (node (ref "C1") (pin "P$2") (pinfunction "2_P$2") (pintype "passive"))
      (node (ref "C11") (pin "P$2") (pinfunction "2_P$2") (pintype "passive"))
      (node (ref "C12") (pin "P$2") (pinfunction "2_P$2") (pintype "passive"))
      (node (ref "C13") (pin "P$1") (pinfunction "1_P$1") (pintype "passive"))
      (node (ref "C14") (pin "P$2") (pinfunction "2_P$2") (pintype "passive"))
      (node (ref "C15") (pin "P$2") (pinfunction "2_P$2") (pintype "passive"))
      (node (ref "C16") (pin "P$2") (pinfunction "2_P$2") (pintype "passive"))
      (node (ref "C17") (pin "P$2") (pinfunction "2_P$2") (pintype "passive"))
      (node (ref "C19") (pin "P$1") (pinfunction "1_P$1") (pintype "passive"))
      (node (ref "C21") (pin "P$2") (pinfunction "2_P$2") (pintype "passive"))
      (node (ref "C23") (pin "P$2") (pinfunction "2_P$2") (pintype "passive"))
      (node (ref "C24") (pin "P$2") (pinfunction "2_P$2") (pintype "passive"))
      (node (ref "C25") (pin "P$2") (pinfunction "2_P$2") (pintype "passive"))
      (node (ref "C26") (pin "P$2") (pinfunction "2_P$2") (pintype "passive"))
      (node (ref "C27") (pin "P$2") (pinfunction "2_P$2") (pintype "passive"))
      (node (ref "C28") (pin "P$2") (pinfunction "2_P$2") (pintype "passive"))
      (node (ref "C30") (pin "P$2") (pinfunction "2_P$2") (pintype "passive"))
      (node (ref "C31") (pin "P$1") (pinfunction "1_P$1") (pintype "passive"))
      (node (ref "C32") (pin "P$2") (pinfunction "2_P$2") (pintype "passive"))
      (node (ref "C33") (pin "P$1") (pinfunction "1_P$1") (pintype "passive"))
      (node (ref "C34") (pin "P$2") (pinfunction "2_P$2") (pintype "passive"))
      (node (ref "C36") (pin "P$2") (pinfunction "2_P$2") (pintype "passive"))
      (node (ref "C37") (pin "P$2") (pinfunction "2_P$2") (pintype "passive"))
      (node (ref "C38") (pin "P$2") (pinfunction "2_P$2") (pintype "passive"))
      (node (ref "C39") (pin "P$2") (pinfunction "2_P$2") (pintype "passive"))
      (node (ref "C4") (pin "P$2") (pinfunction "2_P$2") (pintype "passive"))
      (node (ref "C42") (pin "P$2") (pinfunction "2_P$2") (pintype "passive"))
      (node (ref "C43") (pin "P$2") (pinfunction "2_P$2") (pintype "passive"))
      (node (ref "C46") (pin "P$2") (pinfunction "2_P$2") (pintype "passive"))
      (node (ref "C47") (pin "P$2") (pinfunction "2_P$2") (pintype "passive"))
      (node (ref "C49") (pin "P$2") (pinfunction "2_P$2") (pintype "passive"))
      (node (ref "C5") (pin "P$2") (pinfunction "2_P$2") (pintype "passive"))
      (node (ref "C52") (pin "P$2") (pinfunction "2_P$2") (pintype "passive"))
      (node (ref "C53") (pin "P$2") (pinfunction "2_P$2") (pintype "passive"))
      (node (ref "C6") (pin "P$2") (pinfunction "2_P$2") (pintype "passive"))
      (node (ref "C7") (pin "P$2") (pinfunction "2_P$2") (pintype "passive"))
      (node (ref "C8") (pin "P$2") (pinfunction "2_P$2") (pintype "passive"))
      (node (ref "C9") (pin "P$2") (pinfunction "2_P$2") (pintype "passive"))
      (node (ref "D1") (pin "A") (pinfunction "A_A") (pintype "passive"))
      (node (ref "GND1") (pin "TP") (pinfunction "TP_TP") (pintype "input"))
      (node (ref "GND2") (pin "TP") (pinfunction "TP_TP") (pintype "input"))
      (node (ref "J$1") (pin "GND@0") (pinfunction "GND_GND@0") (pintype "bidirectional"))
      (node (ref "J$1") (pin "GND@1") (pinfunction "GND_GND@1") (pintype "bidirectional"))
      (node (ref "J$1") (pin "GND@2") (pinfunction "GND_GND@2") (pintype "bidirectional"))
      (node (ref "J$1") (pin "GND@3") (pinfunction "GND_GND@3") (pintype "bidirectional"))
      (node (ref "JLINK") (pin "1") (pinfunction "1_1") (pintype "passive"))
      (node (ref "JP1") (pin "7") (pinfunction "7_7") (pintype "bidirectional"))
      (node (ref "JP1") (pin "8") (pinfunction "8_8") (pintype "bidirectional"))
      (node (ref "L16") (pin "P$1") (pinfunction "1_P$1") (pintype "passive"))
      (node (ref "L22") (pin "P$1") (pinfunction "1_P$1") (pintype "passive"))
      (node (ref "R10") (pin "1") (pinfunction "1_1") (pintype "passive"))
      (node (ref "R12") (pin "1") (pinfunction "1_1") (pintype "passive"))
      (node (ref "R2") (pin "1") (pinfunction "1_1") (pintype "passive"))
      (node (ref "R23") (pin "2") (pinfunction "2_2") (pintype "passive"))
      (node (ref "R4") (pin "1") (pinfunction "1_1") (pintype "passive"))
      (node (ref "R9") (pin "1") (pinfunction "1_1") (pintype "passive"))
      (node (ref "S1") (pin "P$2") (pinfunction "S2_P$2") (pintype "bidirectional"))
      (node (ref "TP2") (pin "TP") (pinfunction "TP_TP") (pintype "input"))
      (node (ref "TP3") (pin "TP") (pinfunction "TP_TP") (pintype "input"))
      (node (ref "TP4") (pin "TP") (pinfunction "TP_TP") (pintype "input"))
      (node (ref "TP5") (pin "TP") (pinfunction "TP_TP") (pintype "input"))
      (node (ref "TP6") (pin "TP") (pinfunction "TP_TP") (pintype "input"))
      (node (ref "TP7") (pin "TP") (pinfunction "TP_TP") (pintype "input"))
      (node (ref "TP8") (pin "TP") (pinfunction "TP_TP") (pintype "input"))
      (node (ref "TP9") (pin "TP") (pinfunction "TP_TP") (pintype "input"))
      (node (ref "U1") (pin "2") (pinfunction "GND_2") (pintype "bidirectional"))
      (node (ref "U11") (pin "EXP") (pinfunction "PAD_EXP") (pintype "bidirectional"))
      (node (ref "U12") (pin "EXP") (pinfunction "PAD_EXP") (pintype "bidirectional"))
      (node (ref "U13") (pin "16") (pinfunction "VSS_16") (pintype "bidirectional"))
      (node (ref "U13") (pin "32") (pinfunction "VSS_32") (pintype "bidirectional"))
      (node (ref "U13") (pin "EXP") (pinfunction "PAD_EXP") (pintype "bidirectional"))
      (node (ref "U15") (pin "P$1") (pinfunction "GND_P$1") (pintype "bidirectional"))
      (node (ref "U15") (pin "P$10") (pinfunction "GND_P$10") (pintype "bidirectional"))
      (node (ref "U15") (pin "P$12") (pinfunction "GND_P$12") (pintype "bidirectional"))
      (node (ref "U15") (pin "P$13") (pinfunction "GND_P$13") (pintype "bidirectional"))
      (node (ref "U15") (pin "P$3") (pinfunction "GND_P$3") (pintype "bidirectional"))
      (node (ref "U15") (pin "P$4") (pinfunction "GND_P$4") (pintype "bidirectional"))
      (node (ref "U15") (pin "P$6") (pinfunction "GND_P$6") (pintype "bidirectional"))
      (node (ref "U3") (pin "P$4") (pinfunction "GND_P$4") (pintype "bidirectional"))
      (node (ref "U3") (pin "P$7") (pinfunction "GND_P$7") (pintype "bidirectional"))
      (node (ref "U4") (pin "4") (pinfunction "S_4") (pintype "bidirectional"))
      (node (ref "U5") (pin "2") (pinfunction "GND_2") (pintype "input"))
      (node (ref "U6") (pin "2") (pinfunction "GND_2") (pintype "bidirectional"))
      (node (ref "U7") (pin "2") (pinfunction "S_2") (pintype "passive"))
      (node (ref "U7") (pin "2@1") (pinfunction "PAD_2@1") (pintype "bidirectional"))
      (node (ref "U8") (pin "P$10") (pinfunction "GND_P$10") (pintype "bidirectional"))
      (node (ref "U8") (pin "P$2") (pinfunction "GND_P$2") (pintype "bidirectional"))
      (node (ref "U8") (pin "P$20") (pinfunction "GND_P$20") (pintype "bidirectional"))
      (node (ref "U9") (pin "4") (pinfunction "S_4") (pintype "bidirectional"))
      (node (ref "X1") (pin "2") (pinfunction "G2_2") (pintype "power_in"))
      (node (ref "X1") (pin "4") (pinfunction "G1_4") (pintype "power_in"))
      (node (ref "X2") (pin "2") (pinfunction "G2_2") (pintype "power_in"))
      (node (ref "X2") (pin "4") (pinfunction "G1_4") (pintype "power_in"))
    )
    (net (code "8") (name "GNSS_1PPS") (class "Default")
      (node (ref "U8") (pin "P$11") (pinfunction "TM_P$11") (pintype "bidirectional"))
      (node (ref "U9") (pin "5") (pinfunction "G_5") (pintype "bidirectional"))
    )
    (net (code "9") (name "GNSS_EN") (class "Default")
      (node (ref "R9") (pin "2") (pinfunction "2_2") (pintype "passive"))
      (node (ref "U13") (pin "2") (pinfunction "OSC_IN/PC14_2") (pintype "bidirectional"))
      (node (ref "U4") (pin "2") (pinfunction "G_2") (pintype "bidirectional"))
    )
    (net (code "10") (name "GNSS_EN_1V8") (class "Default")
      (node (ref "R10") (pin "2") (pinfunction "2_2") (pintype "passive"))
      (node (ref "U4") (pin "1") (pinfunction "S_1") (pintype "bidirectional"))
      (node (ref "U8") (pin "P$6") (pinfunction "ON_OFF_P$6") (pintype "bidirectional"))
    )
    (net (code "11") (name "GNSS_UART_TX") (class "Default")
      (node (ref "R15") (pin "1") (pinfunction "1_1") (pintype "passive"))
      (node (ref "U8") (pin "P$15") (pinfunction "TX_P$15") (pintype "bidirectional"))
      (node (ref "U9") (pin "1") (pinfunction "S_1") (pintype "bidirectional"))
    )
    (net (code "12") (name "I2C_SCL") (class "Default")
      (node (ref "U13") (pin "29") (pinfunction "PB6_29") (pintype "bidirectional"))
      (node (ref "U6") (pin "1") (pinfunction "SCL_1") (pintype "bidirectional"))
    )
    (net (code "13") (name "I2C_SDA") (class "Default")
      (node (ref "U13") (pin "30") (pinfunction "PB7_30") (pintype "bidirectional"))
      (node (ref "U6") (pin "3") (pinfunction "SDA_3") (pintype "bidirectional"))
    )
    (net (code "14") (name "MCU_GNSS_1PPS") (class "Default")
      (node (ref "U13") (pin "8") (pinfunction "PA2_8") (pintype "bidirectional"))
      (node (ref "U9") (pin "3") (pinfunction "D_3") (pintype "bidirectional"))
    )
    (net (code "15") (name "MCU_GNSS_UART_RX") (class "Default")
      (node (ref "R16") (pin "1") (pinfunction "1_1") (pintype "passive"))
      (node (ref "U13") (pin "9") (pinfunction "PA3_9") (pintype "bidirectional"))
      (node (ref "U9") (pin "6") (pinfunction "D_6") (pintype "bidirectional"))
    )
    (net (code "16") (name "MCU_UART_RX") (class "Default")
      (node (ref "JP1") (pin "3") (pinfunction "3_3") (pintype "bidirectional"))
      (node (ref "RX") (pin "TP") (pinfunction "TP_TP") (pintype "input"))
      (node (ref "U13") (pin "20") (pinfunction "PA10_20") (pintype "bidirectional"))
    )
    (net (code "17") (name "MCU_UART_TX") (class "Default")
      (node (ref "JP1") (pin "6") (pinfunction "6_6") (pintype "bidirectional"))
      (node (ref "TX") (pin "TP") (pinfunction "TP_TP") (pintype "input"))
      (node (ref "U13") (pin "19") (pinfunction "PA9_19") (pintype "bidirectional"))
    )
    (net (code "18") (name "MISO") (class "Default")
      (node (ref "U11") (pin "13") (pinfunction "SDO_13") (pintype "output"))
      (node (ref "U12") (pin "13") (pinfunction "SDO_13") (pintype "output"))
      (node (ref "U13") (pin "12") (pinfunction "PA6_12") (pintype "bidirectional"))
    )
    (net (code "19") (name "MOSI") (class "Default")
      (node (ref "U11") (pin "14") (pinfunction "SDI_14") (pintype "input"))
      (node (ref "U12") (pin "14") (pinfunction "SDI_14") (pintype "input"))
      (node (ref "U13") (pin "13") (pinfunction "PA7_13") (pintype "bidirectional"))
    )
    (net (code "20") (name "NRST") (class "Default")
      (node (ref "JLINK") (pin "2") (pinfunction "2_2") (pintype "passive"))
      (node (ref "NRST") (pin "TP") (pinfunction "TP_TP") (pintype "input"))
      (node (ref "S1") (pin "P$1") (pinfunction "S1_P$1") (pintype "bidirectional"))
      (node (ref "U13") (pin "4") (pinfunction "NRST_4") (pintype "bidirectional"))
    )
    (net (code "21") (name "Net-(C2-1)") (class "Default")
      (node (ref "C2") (pin "P$1") (pinfunction "1_P$1") (pintype "passive"))
      (node (ref "U1") (pin "1") (pinfunction "BS_1") (pintype "bidirectional"))
    )
    (net (code "22") (name "Net-(C2-2)") (class "Default")
      (node (ref "C2") (pin "P$2") (pinfunction "2_P$2") (pintype "passive"))
      (node (ref "D1") (pin "C") (pinfunction "C_C") (pintype "passive"))
      (node (ref "L12") (pin "P$1") (pinfunction "1_P$1") (pintype "passive"))
      (node (ref "U1") (pin "6") (pinfunction "SW_6") (pintype "bidirectional"))
    )
    (net (code "23") (name "Net-(C10-1)") (class "Default")
      (node (ref "C10") (pin "P$1") (pinfunction "1_P$1") (pintype "passive"))
      (node (ref "C13") (pin "P$2") (pinfunction "2_P$2") (pintype "passive"))
      (node (ref "L14") (pin "P$1") (pinfunction "1_P$1") (pintype "passive"))
      (node (ref "L22") (pin "P$2") (pinfunction "2_P$2") (pintype "passive"))
    )
    (net (code "24") (name "Net-(C10-2)") (class "Default")
      (node (ref "C10") (pin "P$2") (pinfunction "2_P$2") (pintype "passive"))
      (node (ref "L21") (pin "P$2") (pinfunction "2_P$2") (pintype "passive"))
    )
    (net (code "25") (name "Net-(C11-1)") (class "Default")
      (node (ref "C11") (pin "P$1") (pinfunction "1_P$1") (pintype "passive"))
      (node (ref "L17") (pin "P$2") (pinfunction "2_P$2") (pintype "passive"))
      (node (ref "R11") (pin "1") (pinfunction "1_1") (pintype "passive"))
      (node (ref "R12") (pin "2") (pinfunction "2_2") (pintype "passive"))
    )
    (net (code "26") (name "Net-(C18-1)") (class "Default")
      (node (ref "C18") (pin "P$1") (pinfunction "1_P$1") (pintype "passive"))
      (node (ref "L8") (pin "P$1") (pinfunction "1_P$1") (pintype "passive"))
      (node (ref "U11") (pin "2") (pinfunction "RXP_2") (pintype "input"))
    )
    (net (code "27") (name "Net-(C19-2)") (class "Default")
      (node (ref "C19") (pin "P$2") (pinfunction "2_P$2") (pintype "passive"))
      (node (ref "L8") (pin "P$2") (pinfunction "2_P$2") (pintype "passive"))
      (node (ref "U11") (pin "3") (pinfunction "RXN_3") (pintype "input"))
    )
    (net (code "28") (name "Net-(C20-1)") (class "Default")
      (node (ref "C20") (pin "P$1") (pinfunction "1_P$1") (pintype "passive"))
      (node (ref "L13") (pin "P$1") (pinfunction "1_P$1") (pintype "passive"))
      (node (ref "U12") (pin "2") (pinfunction "RXP_2") (pintype "input"))
    )
    (net (code "29") (name "Net-(C21-1)") (class "Default")
      (node (ref "C21") (pin "P$1") (pinfunction "1_P$1") (pintype "passive"))
      (node (ref "L5") (pin "P$1") (pinfunction "1_P$1") (pintype "passive"))
      (node (ref "R22") (pin "1") (pinfunction "1_1") (pintype "passive"))
    )
    (net (code "30") (name "Net-(C22-1)") (class "Default")
      (node (ref "C22") (pin "P$1") (pinfunction "1_P$1") (pintype "passive"))
      (node (ref "L5") (pin "P$2") (pinfunction "2_P$2") (pintype "passive"))
      (node (ref "U11") (pin "4") (pinfunction "TX_4") (pintype "output"))
    )
    (net (code "31") (name "Net-(C22-2)") (class "Default")
      (node (ref "C22") (pin "P$2") (pinfunction "2_P$2") (pintype "passive"))
      (node (ref "L1") (pin "P$1") (pinfunction "1_P$1") (pintype "passive"))
    )
    (net (code "32") (name "Net-(C23-1)") (class "Default")
      (node (ref "C23") (pin "P$1") (pinfunction "1_P$1") (pintype "passive"))
      (node (ref "L1") (pin "P$2") (pinfunction "2_P$2") (pintype "passive"))
      (node (ref "L6") (pin "P$1") (pinfunction "1_P$1") (pintype "passive"))
    )
    (net (code "33") (name "Net-(C24-1)") (class "Default")
      (node (ref "C24") (pin "P$1") (pinfunction "1_P$1") (pintype "passive"))
      (node (ref "L6") (pin "P$2") (pinfunction "2_P$2") (pintype "passive"))
      (node (ref "L7") (pin "P$1") (pinfunction "1_P$1") (pintype "passive"))
    )
    (net (code "34") (name "Net-(C25-1)") (class "Default")
      (node (ref "C25") (pin "P$1") (pinfunction "1_P$1") (pintype "passive"))
      (node (ref "L11") (pin "P$1") (pinfunction "1_P$1") (pintype "passive"))
      (node (ref "L7") (pin "P$2") (pinfunction "2_P$2") (pintype "passive"))
    )
    (net (code "35") (name "Net-(C29-2)") (class "Default")
      (node (ref "C29") (pin "P$2") (pinfunction "2_P$2") (pintype "passive"))
      (node (ref "C30") (pin "P$1") (pinfunction "1_P$1") (pintype "passive"))
      (node (ref "L3") (pin "P$1") (pinfunction "1_P$1") (pintype "passive"))
    )
    (net (code "36") (name "Net-(C31-2)") (class "Default")
      (node (ref "C31") (pin "P$2") (pinfunction "2_P$2") (pintype "passive"))
      (node (ref "L13") (pin "P$2") (pinfunction "2_P$2") (pintype "passive"))
      (node (ref "U12") (pin "3") (pinfunction "RXN_3") (pintype "input"))
    )
    (net (code "37") (name "Net-(C33-2)") (class "Default")
      (node (ref "C33") (pin "P$2") (pinfunction "2_P$2") (pintype "passive"))
      (node (ref "C35") (pin "P$1") (pinfunction "1_P$1") (pintype "passive"))
      (node (ref "C40") (pin "P$2") (pinfunction "2_P$2") (pintype "passive"))
      (node (ref "L16") (pin "P$2") (pinfunction "2_P$2") (pintype "passive"))
    )
    (net (code "38") (name "Net-(C35-2)") (class "Default")
      (node (ref "C35") (pin "P$2") (pinfunction "2_P$2") (pintype "passive"))
      (node (ref "L14") (pin "P$2") (pinfunction "2_P$2") (pintype "passive"))
    )
    (net (code "39") (name "Net-(C36-1)") (class "Default")
      (node (ref "C36") (pin "P$1") (pinfunction "1_P$1") (pintype "passive"))
      (node (ref "L10") (pin "P$1") (pinfunction "1_P$1") (pintype "passive"))
      (node (ref "L9") (pin "P$2") (pinfunction "2_P$2") (pintype "passive"))
    )
    (net (code "40") (name "Net-(C37-1)") (class "Default")
      (node (ref "C37") (pin "P$1") (pinfunction "1_P$1") (pintype "passive"))
      (node (ref "C39") (pin "P$1") (pinfunction "1_P$1") (pintype "passive"))
      (node (ref "L4") (pin "P$2") (pinfunction "2_P$2") (pintype "passive"))
      (node (ref "L9") (pin "P$1") (pinfunction "1_P$1") (pintype "passive"))
      (node (ref "U7") (pin "3") (pinfunction "D_3") (pintype "passive"))
    )
    (net (code "41") (name "Net-(C40-1)") (class "Default")
      (node (ref "C40") (pin "P$1") (pinfunction "1_P$1") (pintype "passive"))
      (node (ref "L15") (pin "P$1") (pinfunction "1_P$1") (pintype "passive"))
    )
    (net (code "42") (name "Net-(C42-1)") (class "Default")
      (node (ref "C42") (pin "P$1") (pinfunction "1_P$1") (pintype "passive"))
      (node (ref "C52") (pin "P$1") (pinfunction "1_P$1") (pintype "passive"))
      (node (ref "L10") (pin "P$2") (pinfunction "2_P$2") (pintype "passive"))
      (node (ref "L23") (pin "P$1") (pinfunction "1_P$1") (pintype "passive"))
    )
    (net (code "43") (name "Net-(C43-1)") (class "Default")
      (node (ref "C43") (pin "P$1") (pinfunction "1_P$1") (pintype "passive"))
      (node (ref "C6") (pin "P$1") (pinfunction "1_P$1") (pintype "passive"))
      (node (ref "L2") (pin "P$2") (pinfunction "2_P$2") (pintype "passive"))
      (node (ref "U1") (pin "4") (pinfunction "EN_4") (pintype "bidirectional"))
      (node (ref "U1") (pin "5") (pinfunction "IN_5") (pintype "bidirectional"))
    )
    (net (code "44") (name "Net-(C44-1)") (class "Default")
      (node (ref "C44") (pin "P$1") (pinfunction "1_P$1") (pintype "passive"))
      (node (ref "C53") (pin "P$1") (pinfunction "1_P$1") (pintype "passive"))
      (node (ref "L23") (pin "P$2") (pinfunction "2_P$2") (pintype "passive"))
    )
    (net (code "45") (name "Net-(D2-PadA)") (class "Default")
      (node (ref "D2") (pin "A") (pinfunction "A_A") (pintype "passive"))
      (node (ref "JP1") (pin "1") (pinfunction "1_1") (pintype "bidirectional"))
      (node (ref "JP1") (pin "2") (pinfunction "2_2") (pintype "bidirectional"))
      (node (ref "V_IN") (pin "TP") (pinfunction "TP_TP") (pintype "input"))
    )
    (net (code "46") (name "Net-(D2-PadC)") (class "Default")
      (node (ref "D2") (pin "C") (pinfunction "C_C") (pintype "passive"))
      (node (ref "F1") (pin "1") (pinfunction "1_1") (pintype "passive"))
    )
    (net (code "47") (name "Net-(J$1-SIGNAL)") (class "Default")
      (node (ref "J$1") (pin "SIG") (pinfunction "SIGNAL_SIG") (pintype "bidirectional"))
      (node (ref "TP1") (pin "TP") (pinfunction "TP_TP") (pintype "input"))
      (node (ref "U15") (pin "P$2") (pinfunction "RF1_P$2") (pintype "bidirectional"))
    )
    (net (code "48") (name "Net-(L17-1)") (class "Default")
      (node (ref "L17") (pin "P$1") (pinfunction "1_P$1") (pintype "passive"))
      (node (ref "L3") (pin "P$2") (pinfunction "2_P$2") (pintype "passive"))
      (node (ref "U7") (pin "1") (pinfunction "G_1") (pintype "passive"))
    )
    (net (code "49") (name "Net-(U1-FB)") (class "Default")
      (node (ref "R1") (pin "1") (pinfunction "1_1") (pintype "passive"))
      (node (ref "R2") (pin "2") (pinfunction "2_2") (pintype "passive"))
      (node (ref "U1") (pin "3") (pinfunction "FB_3") (pintype "bidirectional"))
    )
    (net (code "50") (name "Net-(U3-ADJ)") (class "Default")
      (node (ref "R4") (pin "2") (pinfunction "2_2") (pintype "passive"))
      (node (ref "R5") (pin "1") (pinfunction "1_1") (pintype "passive"))
      (node (ref "U3") (pin "P$2") (pinfunction "ADJ_P$2") (pintype "bidirectional"))
    )
    (net (code "51") (name "Net-(U8-GPIO6)") (class "Default")
      (node (ref "R14") (pin "1") (pinfunction "1_1") (pintype "passive"))
      (node (ref "U8") (pin "P$13") (pinfunction "GPIO6_P$13") (pintype "bidirectional"))
    )
    (net (code "52") (name "Net-(U10-RF)") (class "Default")
      (node (ref "U10") (pin "P$1") (pinfunction "RF_P$1") (pintype "bidirectional"))
      (node (ref "U8") (pin "P$1") (pinfunction "RF_IN_P$1") (pintype "bidirectional"))
    )
    (net (code "53") (name "Net-(U11-XIN)") (class "Default")
      (node (ref "U11") (pin "17") (pinfunction "XIN_17") (pintype "input"))
      (node (ref "X1") (pin "3") (pinfunction "X2_3") (pintype "bidirectional"))
    )
    (net (code "54") (name "Net-(U11-XOUT)") (class "Default")
      (node (ref "U11") (pin "16") (pinfunction "XOUT_16") (pintype "bidirectional"))
      (node (ref "X1") (pin "1") (pinfunction "X1_1") (pintype "bidirectional"))
    )
    (net (code "55") (name "Net-(U12-XIN)") (class "Default")
      (node (ref "U12") (pin "17") (pinfunction "XIN_17") (pintype "input"))
      (node (ref "X2") (pin "3") (pinfunction "X2_3") (pintype "bidirectional"))
    )
    (net (code "56") (name "Net-(U12-XOUT)") (class "Default")
      (node (ref "U12") (pin "16") (pinfunction "XOUT_16") (pintype "bidirectional"))
      (node (ref "X2") (pin "1") (pinfunction "X1_1") (pintype "bidirectional"))
    )
    (net (code "57") (name "PA_IN") (class "Default")
      (node (ref "C29") (pin "P$1") (pinfunction "1_P$1") (pintype "passive"))
      (node (ref "L11") (pin "P$2") (pinfunction "2_P$2") (pintype "passive"))
    )
    (net (code "58") (name "PA_OUT") (class "Default")
      (node (ref "C44") (pin "P$2") (pinfunction "2_P$2") (pintype "passive"))
      (node (ref "U15") (pin "P$5") (pinfunction "RF3_P$5") (pintype "bidirectional"))
    )
    (net (code "59") (name "RF_IN") (class "Default")
      (node (ref "L21") (pin "P$1") (pinfunction "1_P$1") (pintype "passive"))
      (node (ref "U15") (pin "P$11") (pinfunction "RF2_P$11") (pintype "bidirectional"))
    )
    (net (code "60") (name "RX_EN") (class "Default")
      (node (ref "R19") (pin "1") (pinfunction "1_1") (pintype "passive"))
      (node (ref "U15") (pin "P$7") (pinfunction "CTRL_P$7") (pintype "bidirectional"))
      (node (ref "U4") (pin "3") (pinfunction "D_3") (pintype "bidirectional"))
    )
    (net (code "61") (name "RX_IC_CLK") (class "Default")
      (node (ref "U12") (pin "20") (pinfunction "GPIO3_20") (pintype "bidirectional"))
      (node (ref "U13") (pin "26") (pinfunction "PB3_26") (pintype "bidirectional"))
    )
    (net (code "62") (name "RX_IC_DATA") (class "Default")
      (node (ref "U12") (pin "10") (pinfunction "GPIO1_10") (pintype "bidirectional"))
      (node (ref "U13") (pin "27") (pinfunction "PB4_27") (pintype "bidirectional"))
    )
    (net (code "63") (name "RX_IN") (class "Default")
      (node (ref "C18") (pin "P$2") (pinfunction "2_P$2") (pintype "passive"))
      (node (ref "C20") (pin "P$2") (pinfunction "2_P$2") (pintype "passive"))
      (node (ref "L15") (pin "P$2") (pinfunction "2_P$2") (pintype "passive"))
    )
    (net (code "64") (name "SCK") (class "Default")
      (node (ref "U11") (pin "12") (pinfunction "SCLK_12") (pintype "input"))
      (node (ref "U12") (pin "12") (pinfunction "SCLK_12") (pintype "input"))
      (node (ref "U13") (pin "11") (pinfunction "PA5_11") (pintype "bidirectional"))
    )
    (net (code "65") (name "SDN1") (class "Default")
      (node (ref "U11") (pin "1") (pinfunction "SDN_1") (pintype "input"))
      (node (ref "U13") (pin "14") (pinfunction "PB0_14") (pintype "bidirectional"))
    )
    (net (code "66") (name "SDN2") (class "Default")
      (node (ref "U12") (pin "1") (pinfunction "SDN_1") (pintype "input"))
      (node (ref "U13") (pin "25") (pinfunction "PA15_25") (pintype "bidirectional"))
    )
    (net (code "67") (name "SPARE") (class "Default")
      (node (ref "JP1") (pin "5") (pinfunction "5_5") (pintype "bidirectional"))
      (node (ref "U13") (pin "21") (pinfunction "PA11_21") (pintype "bidirectional"))
    )
    (net (code "68") (name "SWCLK") (class "Default")
      (node (ref "JLINK") (pin "3") (pinfunction "3_3") (pintype "passive"))
      (node (ref "SWCLK") (pin "TP") (pinfunction "TP_TP") (pintype "input"))
      (node (ref "U13") (pin "24") (pinfunction "PA14_24") (pintype "bidirectional"))
    )
    (net (code "69") (name "SWDIO") (class "Default")
      (node (ref "JLINK") (pin "4") (pinfunction "4_4") (pintype "passive"))
      (node (ref "SWDIO") (pin "TP") (pinfunction "TP_TP") (pintype "input"))
      (node (ref "U13") (pin "23") (pinfunction "PA13_23") (pintype "bidirectional"))
    )
    (net (code "70") (name "TRX_IC_CLOCK") (class "Default")
      (node (ref "U11") (pin "19") (pinfunction "GPIO2_19") (pintype "bidirectional"))
      (node (ref "U13") (pin "7") (pinfunction "PA1_7") (pintype "bidirectional"))
    )
    (net (code "71") (name "TRX_IC_DATA") (class "Default")
      (node (ref "U11") (pin "10") (pinfunction "GPIO1_10") (pintype "bidirectional"))
      (node (ref "U13") (pin "15") (pinfunction "PB1_15") (pintype "bidirectional"))
    )
    (net (code "72") (name "TX_CTRL") (class "Default")
      (node (ref "R11") (pin "2") (pinfunction "2_2") (pintype "passive"))
      (node (ref "U13") (pin "28") (pinfunction "PB5_28") (pintype "bidirectional"))
      (node (ref "U4") (pin "5") (pinfunction "G_5") (pintype "bidirectional"))
    )
    (net (code "73") (name "TX_DISABLE") (class "Default")
      (node (ref "JP1") (pin "4") (pinfunction "4_4") (pintype "bidirectional"))
      (node (ref "U13") (pin "22") (pinfunction "PA12_22") (pintype "bidirectional"))
    )
    (net (code "74") (name "V_BAT") (class "Default")
      (node (ref "C4") (pin "P$1") (pinfunction "1_P$1") (pintype "passive"))
      (node (ref "C47") (pin "P$1") (pinfunction "1_P$1") (pintype "passive"))
      (node (ref "F1") (pin "2") (pinfunction "2_2") (pintype "passive"))
      (node (ref "L2") (pin "P$1") (pinfunction "1_P$1") (pintype "passive"))
      (node (ref "U3") (pin "P$5") (pinfunction "EN_P$5") (pintype "bidirectional"))
      (node (ref "U3") (pin "P$6") (pinfunction "VIN_P$6") (pintype "bidirectional"))
    )
    (net (code "75") (name "V_PA") (class "Default")
      (node (ref "C49") (pin "P$1") (pinfunction "1_P$1") (pintype "passive"))
      (node (ref "C7") (pin "P$1") (pinfunction "1_P$1") (pintype "passive"))
      (node (ref "L4") (pin "P$1") (pinfunction "1_P$1") (pintype "passive"))
      (node (ref "R5") (pin "2") (pinfunction "2_2") (pintype "passive"))
      (node (ref "U3") (pin "P$1") (pinfunction "VOUT_P$1") (pintype "bidirectional"))
      (node (ref "V_PA") (pin "TP") (pinfunction "TP_TP") (pintype "input"))
    )
    (net (code "76") (name "unconnected-(S1-S1-PadP$4)") (class "Default")
      (node (ref "S1") (pin "P$4") (pinfunction "S1_P$4") (pintype "bidirectional"))
    )
    (net (code "77") (name "unconnected-(S1-S2-PadP$3)") (class "Default")
      (node (ref "S1") (pin "P$3") (pinfunction "S2_P$3") (pintype "bidirectional"))
    )
    (net (code "78") (name "unconnected-(U3-PG-PadP$3)") (class "Default")
      (node (ref "U3") (pin "P$3") (pinfunction "PG_P$3") (pintype "bidirectional"))
    )
    (net (code "79") (name "unconnected-(U5-BP-Pad4)") (class "Default")
      (node (ref "U5") (pin "4") (pinfunction "BP_4") (pintype "input"))
    )
    (net (code "80") (name "unconnected-(U8-BOOTSEL-PadP$9)") (class "Default")
      (node (ref "U8") (pin "P$9") (pinfunction "BOOTSEL_P$9") (pintype "bidirectional"))
    )
    (net (code "81") (name "unconnected-(U8-GPIO0-PadP$18)") (class "Default")
      (node (ref "U8") (pin "P$18") (pinfunction "GPIO0_P$18") (pintype "bidirectional"))
    )
    (net (code "82") (name "unconnected-(U8-GPIO1-PadP$17)") (class "Default")
      (node (ref "U8") (pin "P$17") (pinfunction "GPIO1_P$17") (pintype "bidirectional"))
    )
    (net (code "83") (name "unconnected-(U8-GPIO7-PadP$12)") (class "Default")
      (node (ref "U8") (pin "P$12") (pinfunction "GPIO7_P$12") (pintype "bidirectional"))
    )
    (net (code "84") (name "unconnected-(U8-GPIO8-PadP$5)") (class "Default")
      (node (ref "U8") (pin "P$5") (pinfunction "GPIO8_P$5") (pintype "bidirectional"))
    )
    (net (code "85") (name "unconnected-(U8-NC-PadP$4)") (class "Default")
      (node (ref "U8") (pin "P$4") (pinfunction "NC_P$4") (pintype "bidirectional"))
    )
    (net (code "86") (name "unconnected-(U8-NC-PadP$16)") (class "Default")
      (node (ref "U8") (pin "P$16") (pinfunction "NC_P$16") (pintype "bidirectional"))
    )
    (net (code "87") (name "unconnected-(U8-NRESET-PadP$8)") (class "Default")
      (node (ref "U8") (pin "P$8") (pinfunction "NRESET_P$8") (pintype "bidirectional"))
    )
    (net (code "88") (name "unconnected-(U8-RX-PadP$14)") (class "Default")
      (node (ref "U8") (pin "P$14") (pinfunction "RX_P$14") (pintype "bidirectional"))
    )
    (net (code "89") (name "unconnected-(U8-SYS_ON-PadP$7)") (class "Default")
      (node (ref "U8") (pin "P$7") (pinfunction "SYS_ON_P$7") (pintype "bidirectional"))
    )
    (net (code "90") (name "unconnected-(U10-PAD-PadP$2)") (class "Default")
      (node (ref "U10") (pin "P$2") (pinfunction "PAD_P$2") (pintype "bidirectional"))
    )
    (net (code "91") (name "unconnected-(U11-GNDX-Pad18)") (class "Default")
      (node (ref "U11") (pin "18") (pinfunction "GNDX_18") (pintype "bidirectional"))
    )
    (net (code "92") (name "unconnected-(U11-GPIO0-Pad9)") (class "Default")
      (node (ref "U11") (pin "9") (pinfunction "GPIO0_9") (pintype "bidirectional"))
    )
    (net (code "93") (name "unconnected-(U11-GPIO3-Pad20)") (class "Default")
      (node (ref "U11") (pin "20") (pinfunction "GPIO3_20") (pintype "bidirectional"))
    )
    (net (code "94") (name "unconnected-(U11-NIRQ-Pad11)") (class "Default")
      (node (ref "U11") (pin "11") (pinfunction "NIRQ_11") (pintype "bidirectional"))
    )
    (net (code "95") (name "unconnected-(U11-TXRAMP-Pad7)") (class "Default")
      (node (ref "U11") (pin "7") (pinfunction "TXRAMP_7") (pintype "bidirectional"))
    )
    (net (code "96") (name "unconnected-(U12-GNDX-Pad18)") (class "Default")
      (node (ref "U12") (pin "18") (pinfunction "GNDX_18") (pintype "bidirectional"))
    )
    (net (code "97") (name "unconnected-(U12-GPIO0-Pad9)") (class "Default")
      (node (ref "U12") (pin "9") (pinfunction "GPIO0_9") (pintype "bidirectional"))
    )
    (net (code "98") (name "unconnected-(U12-GPIO2-Pad19)") (class "Default")
      (node (ref "U12") (pin "19") (pinfunction "GPIO2_19") (pintype "bidirectional"))
    )
    (net (code "99") (name "unconnected-(U12-NIRQ-Pad11)") (class "Default")
      (node (ref "U12") (pin "11") (pinfunction "NIRQ_11") (pintype "bidirectional"))
    )
    (net (code "100") (name "unconnected-(U12-TX-Pad4)") (class "Default")
      (node (ref "U12") (pin "4") (pinfunction "TX_4") (pintype "output"))
    )
    (net (code "101") (name "unconnected-(U12-TXRAMP-Pad7)") (class "Default")
      (node (ref "U12") (pin "7") (pinfunction "TXRAMP_7") (pintype "bidirectional"))
    )
    (net (code "102") (name "~{EEPROM_WRITE_EN}") (class "Default")
      (node (ref "R6") (pin "2") (pinfunction "2_2") (pintype "passive"))
      (node (ref "U13") (pin "3") (pinfunction "OSC_OUT/PC15_3") (pintype "bidirectional"))
      (node (ref "U6") (pin "5") (pinfunction "WP_5") (pintype "bidirectional"))
    )
  )
)
